# master-v1_0.net
KiCad netlist of a schematic drawn in EAGLE
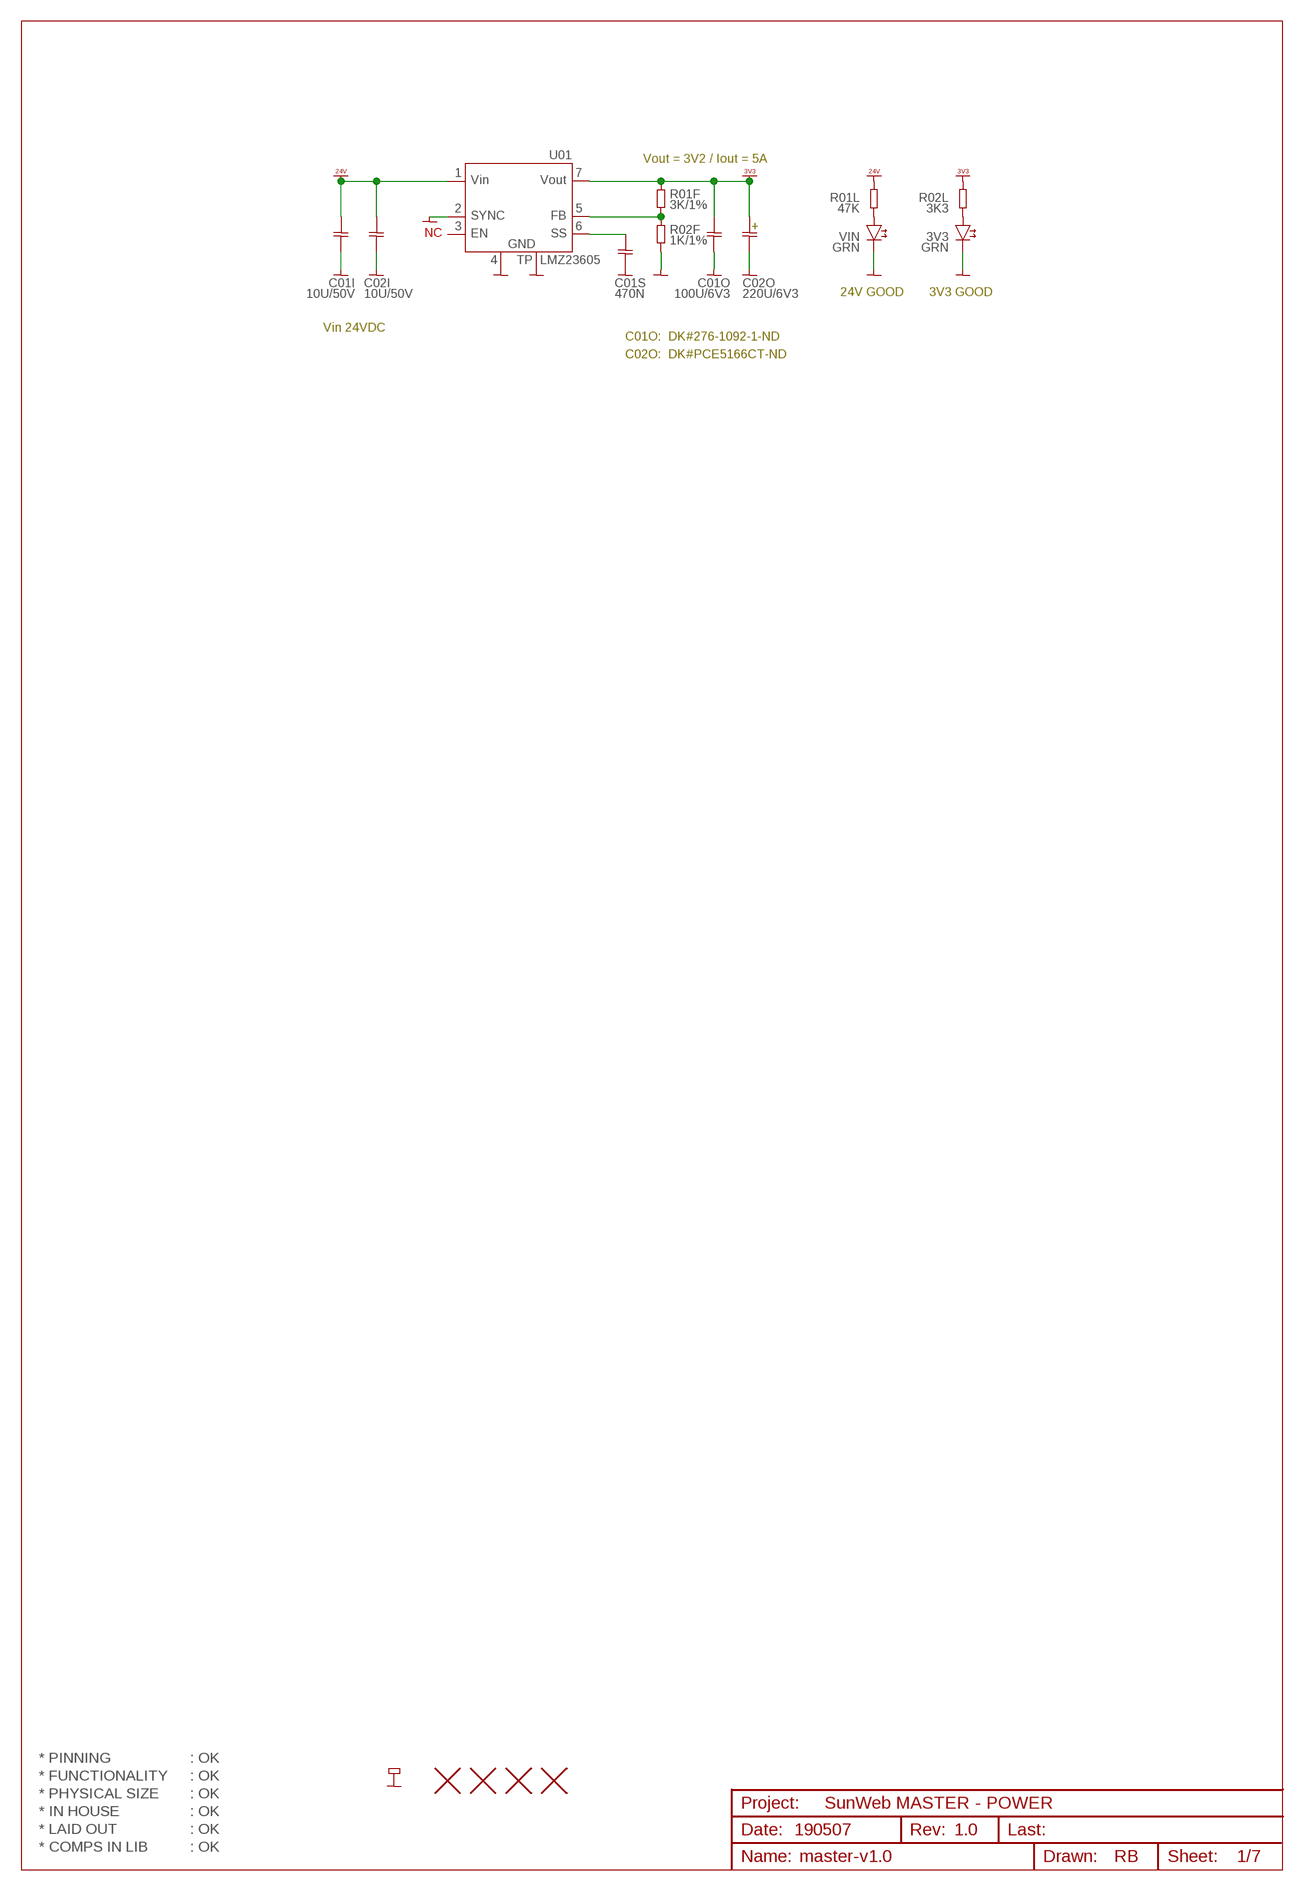
[diagram p0: schematic, sheet 1]
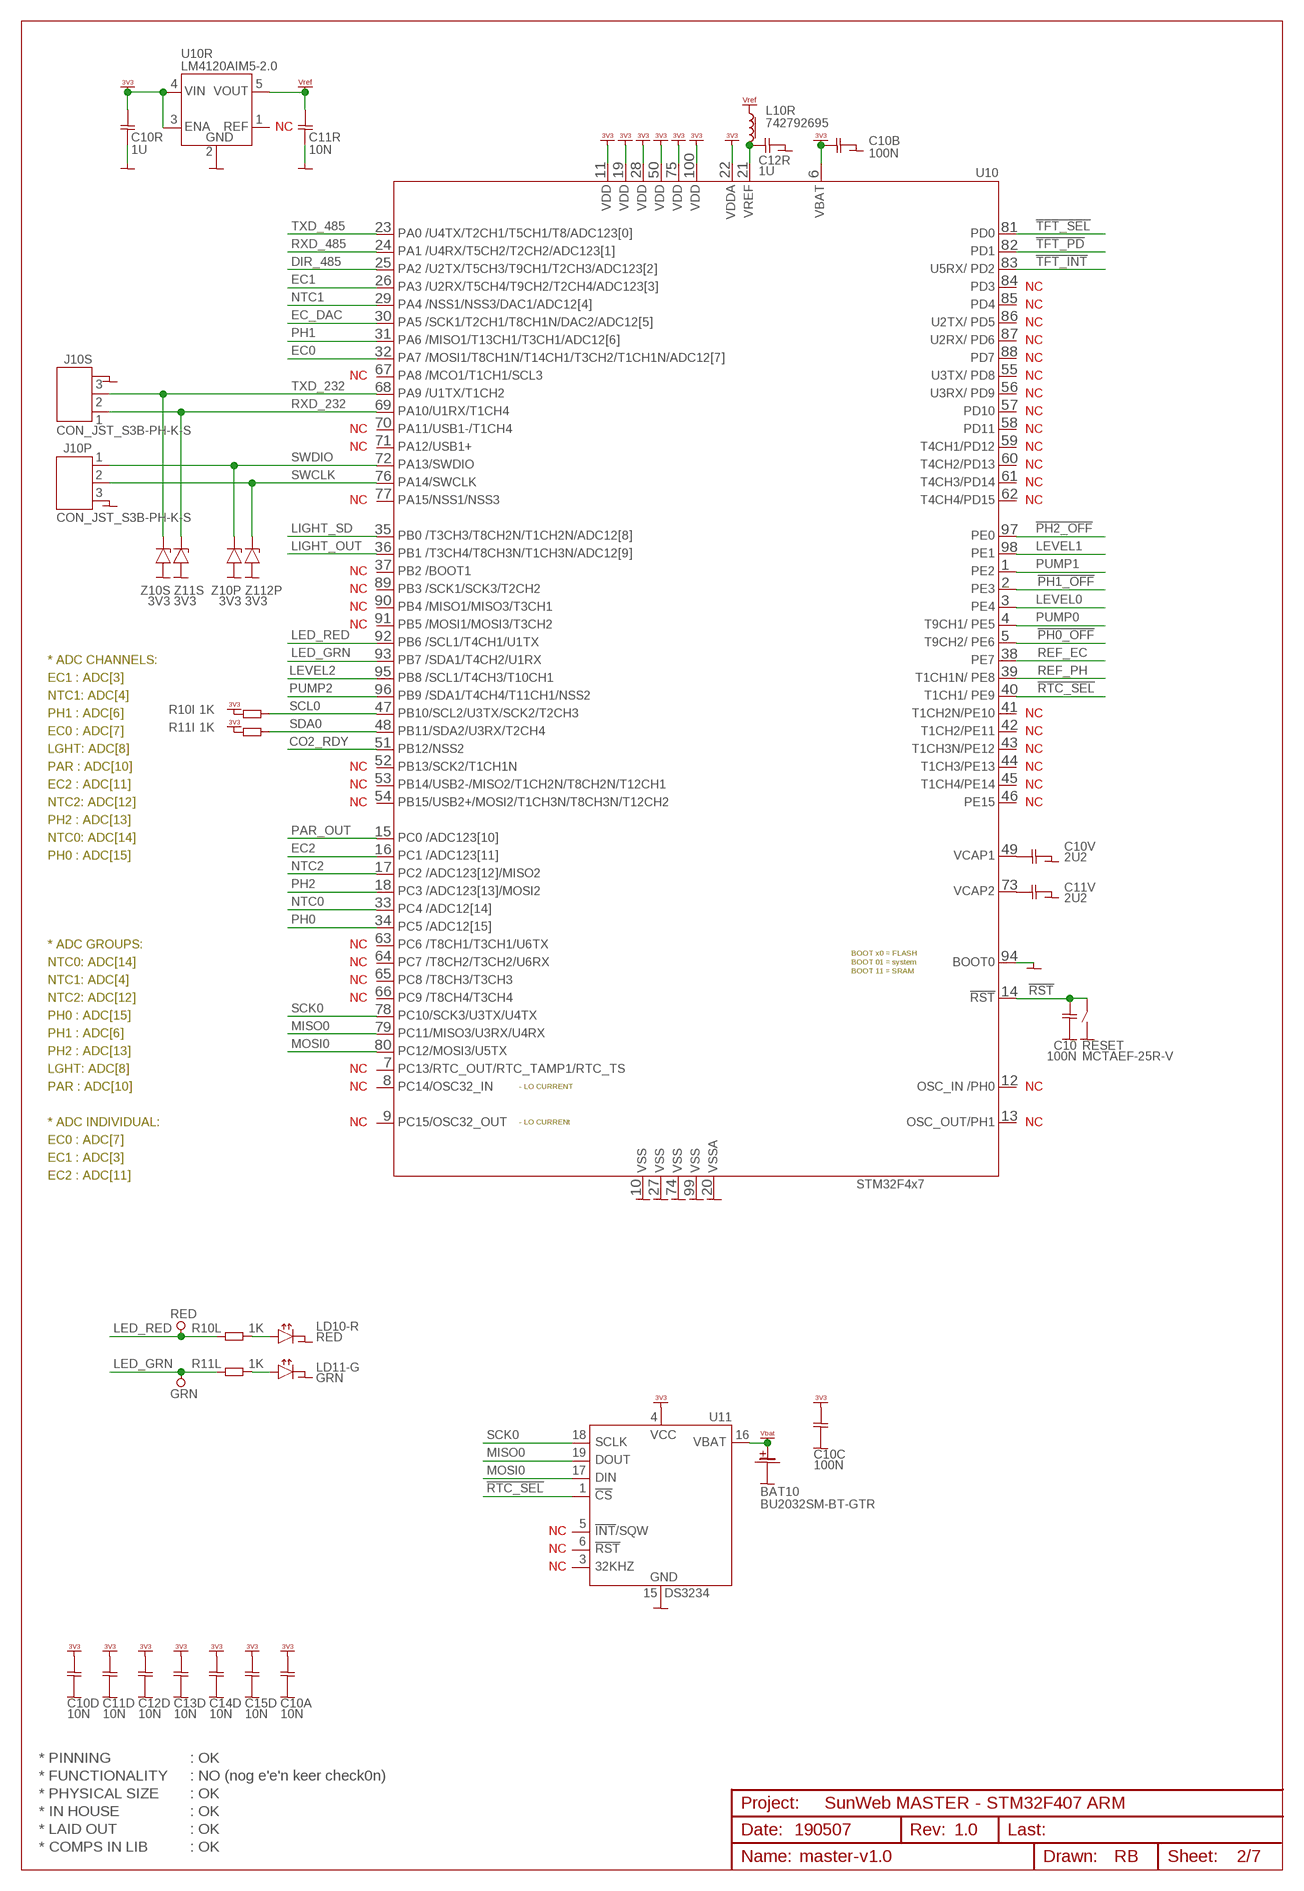
[diagram p1: schematic, sheet 2]
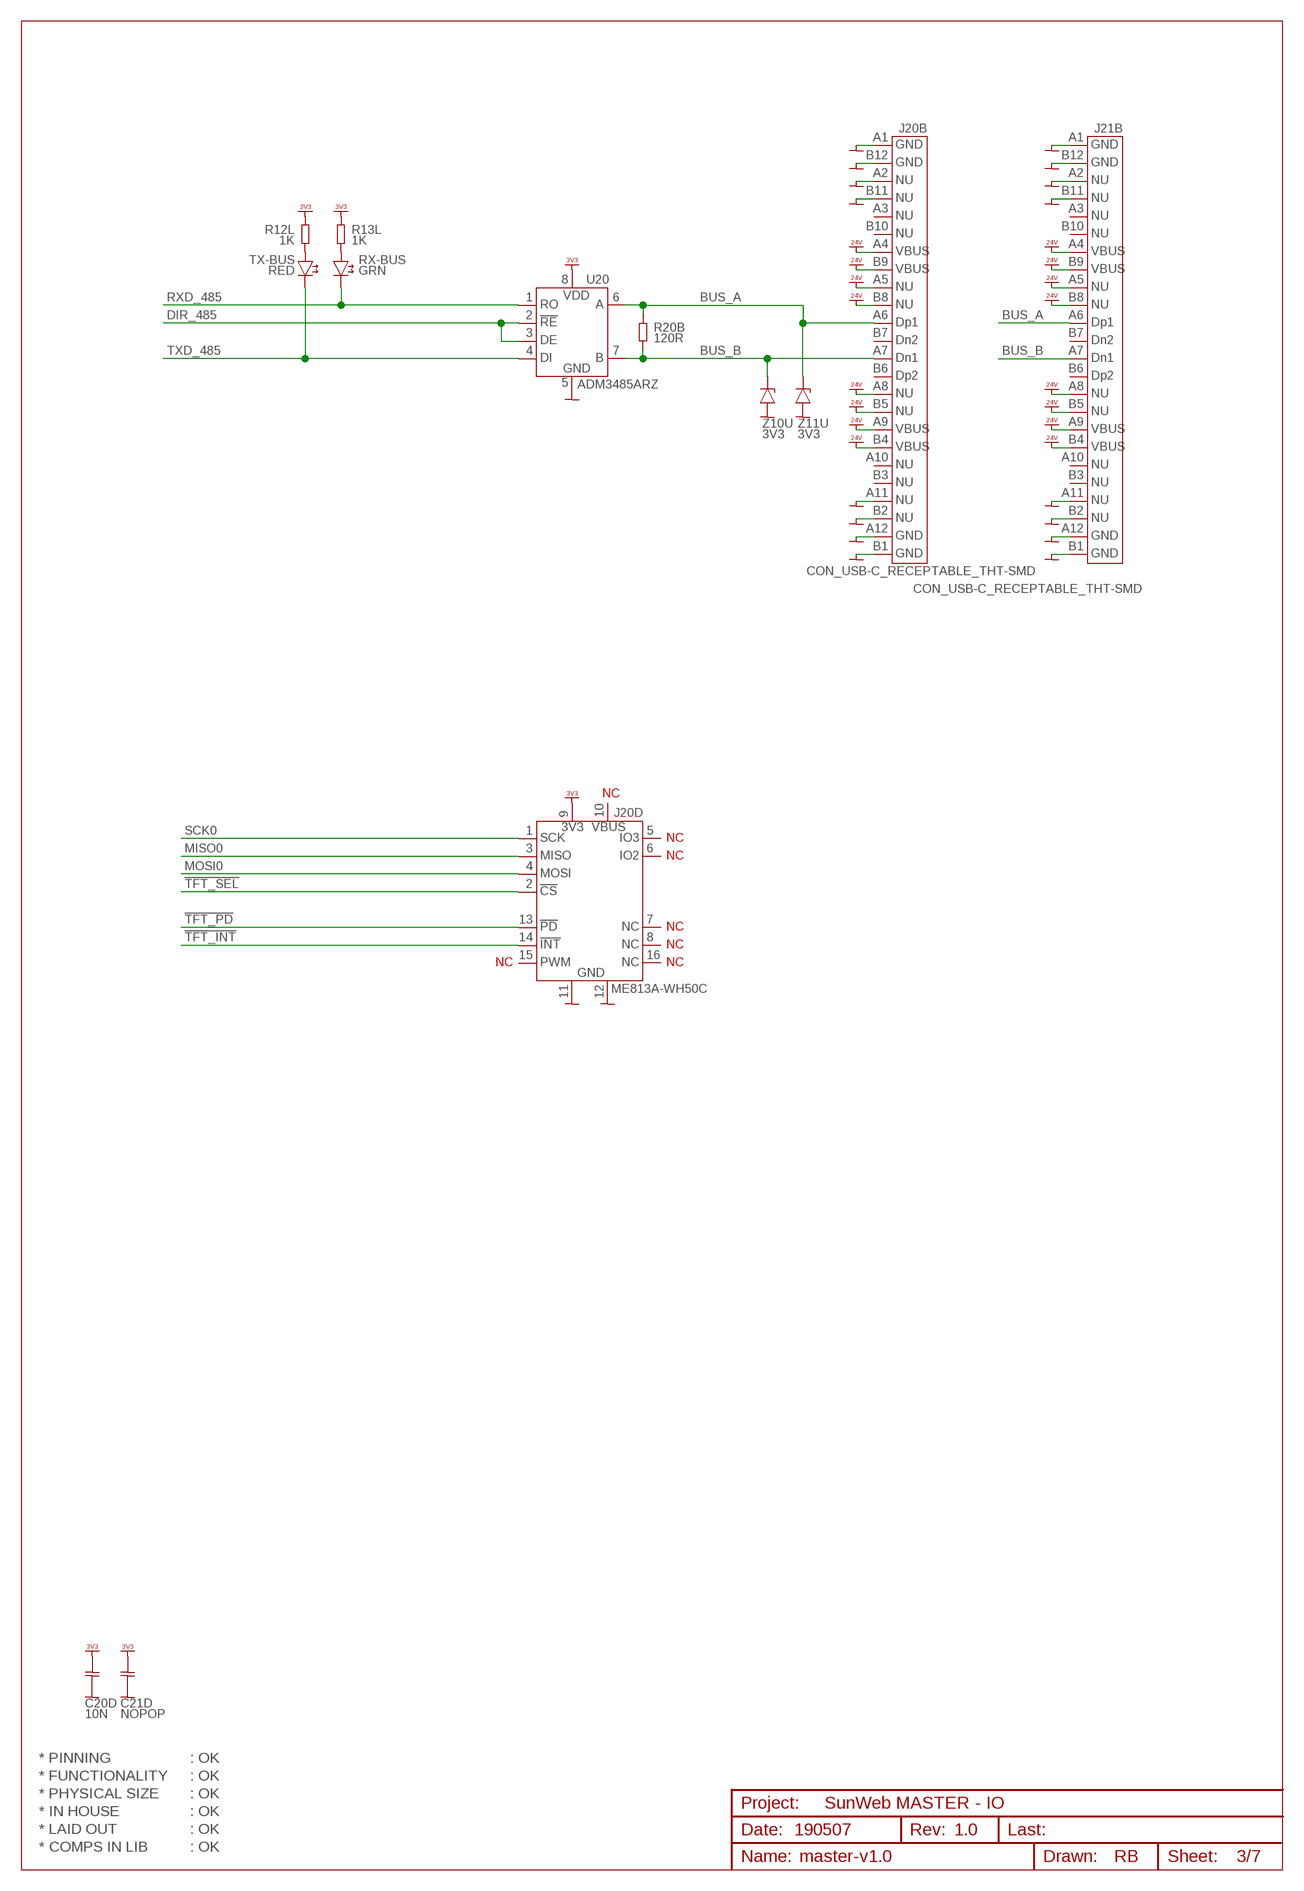
[diagram p2: schematic, sheet 3]
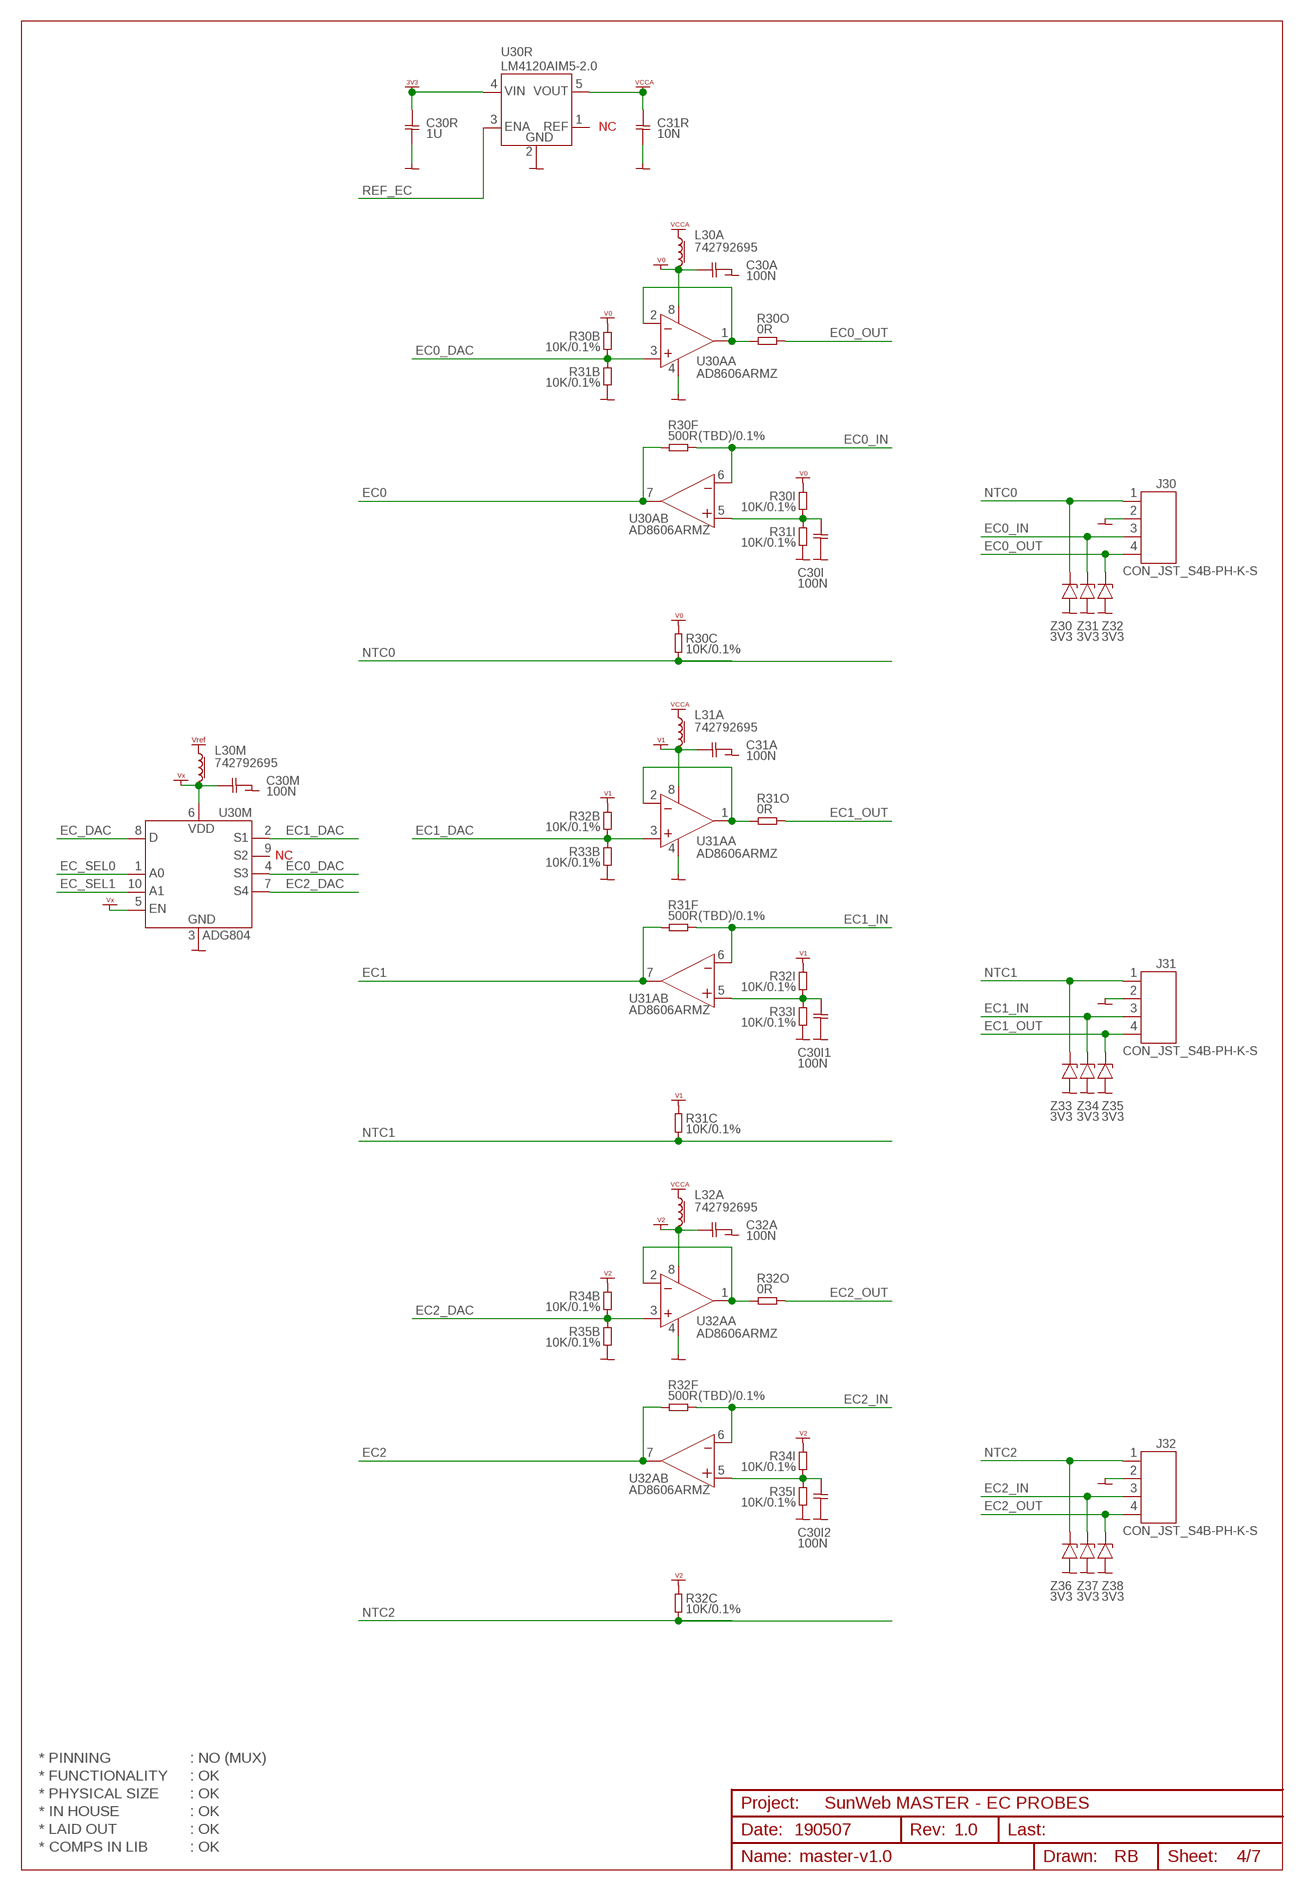
[diagram p3: schematic, sheet 4]
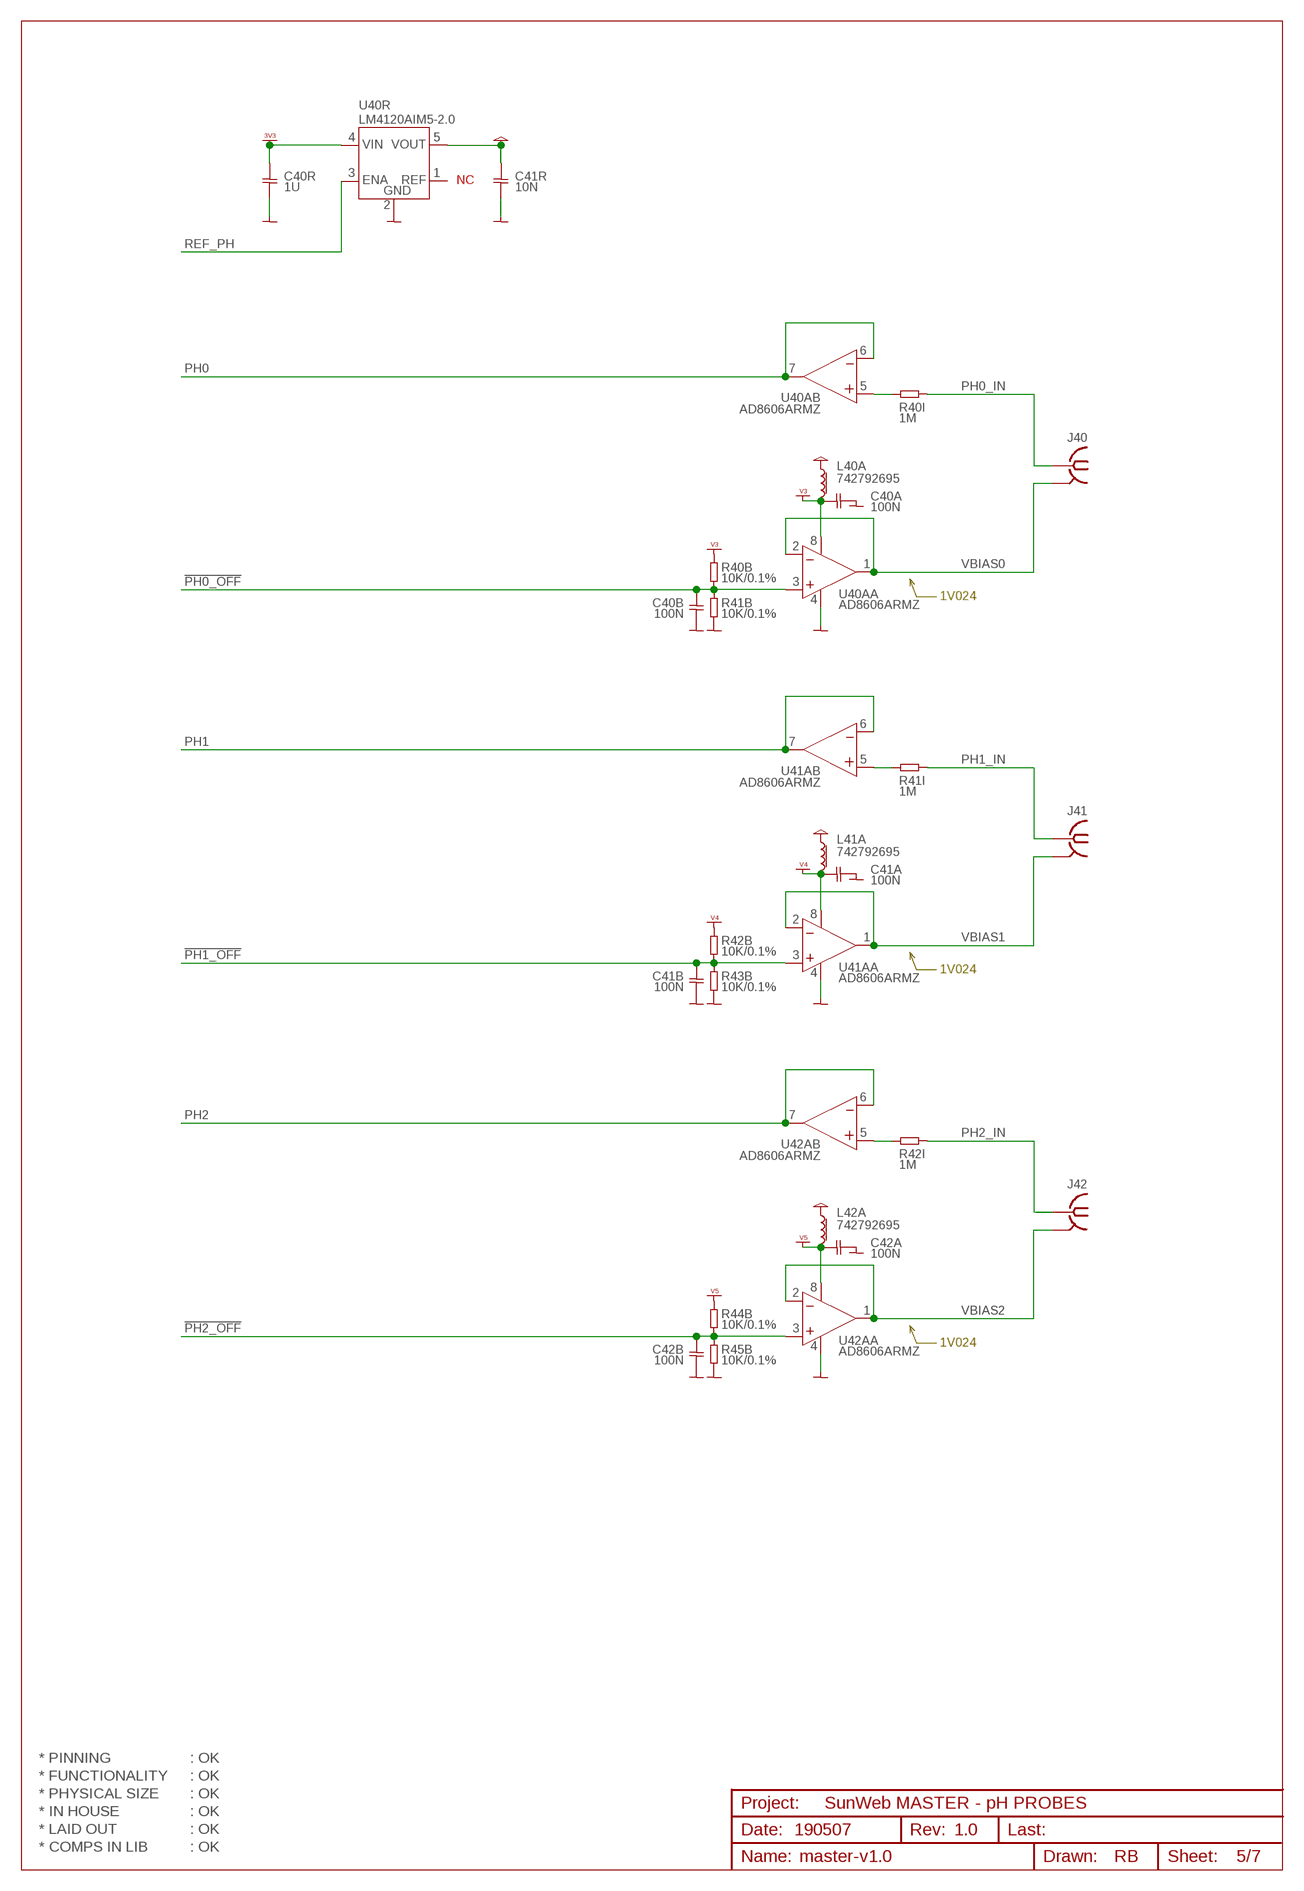
[diagram p4: schematic, sheet 5]
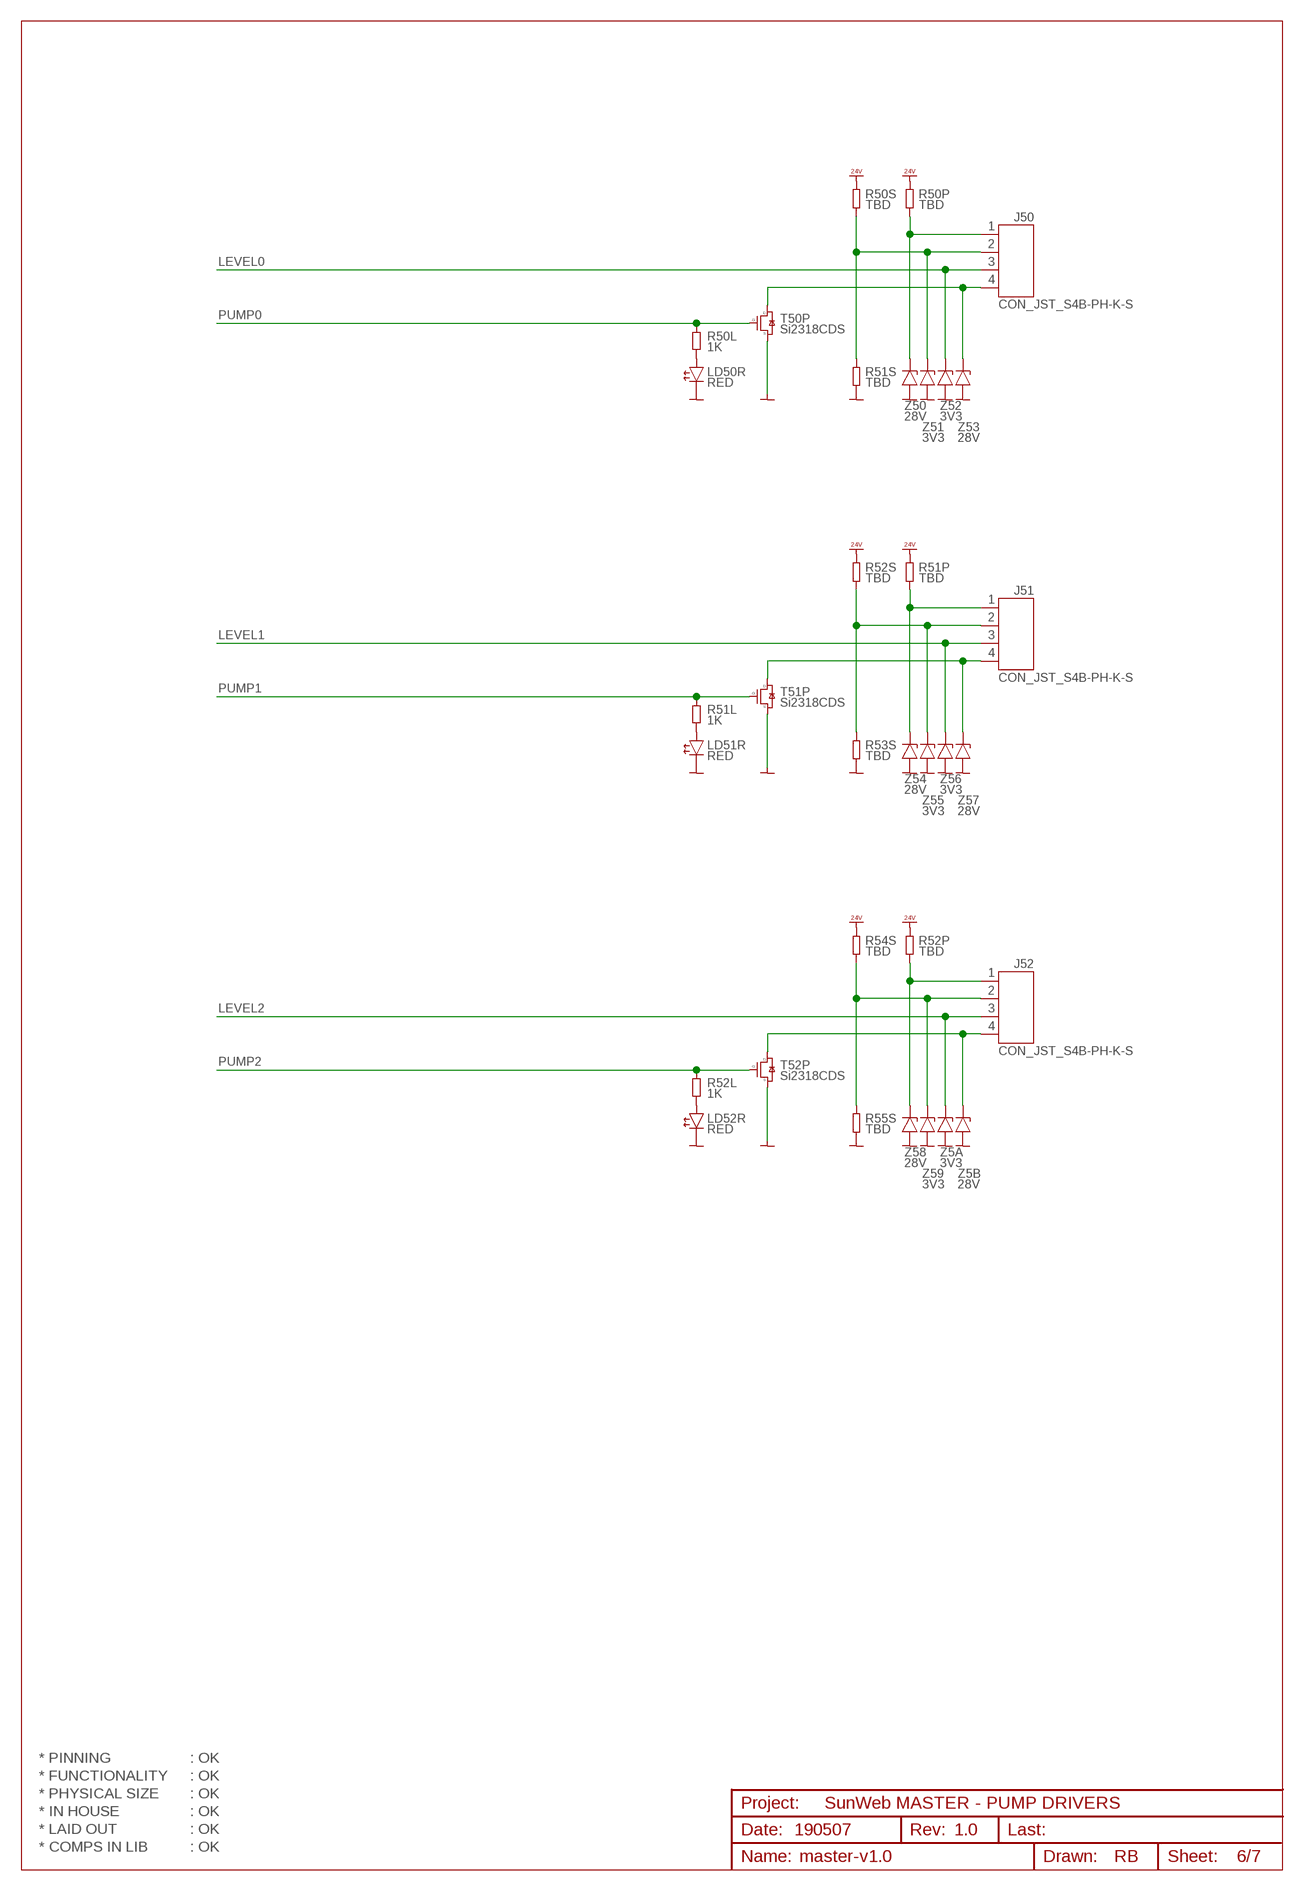
[diagram p5: schematic, sheet 6]
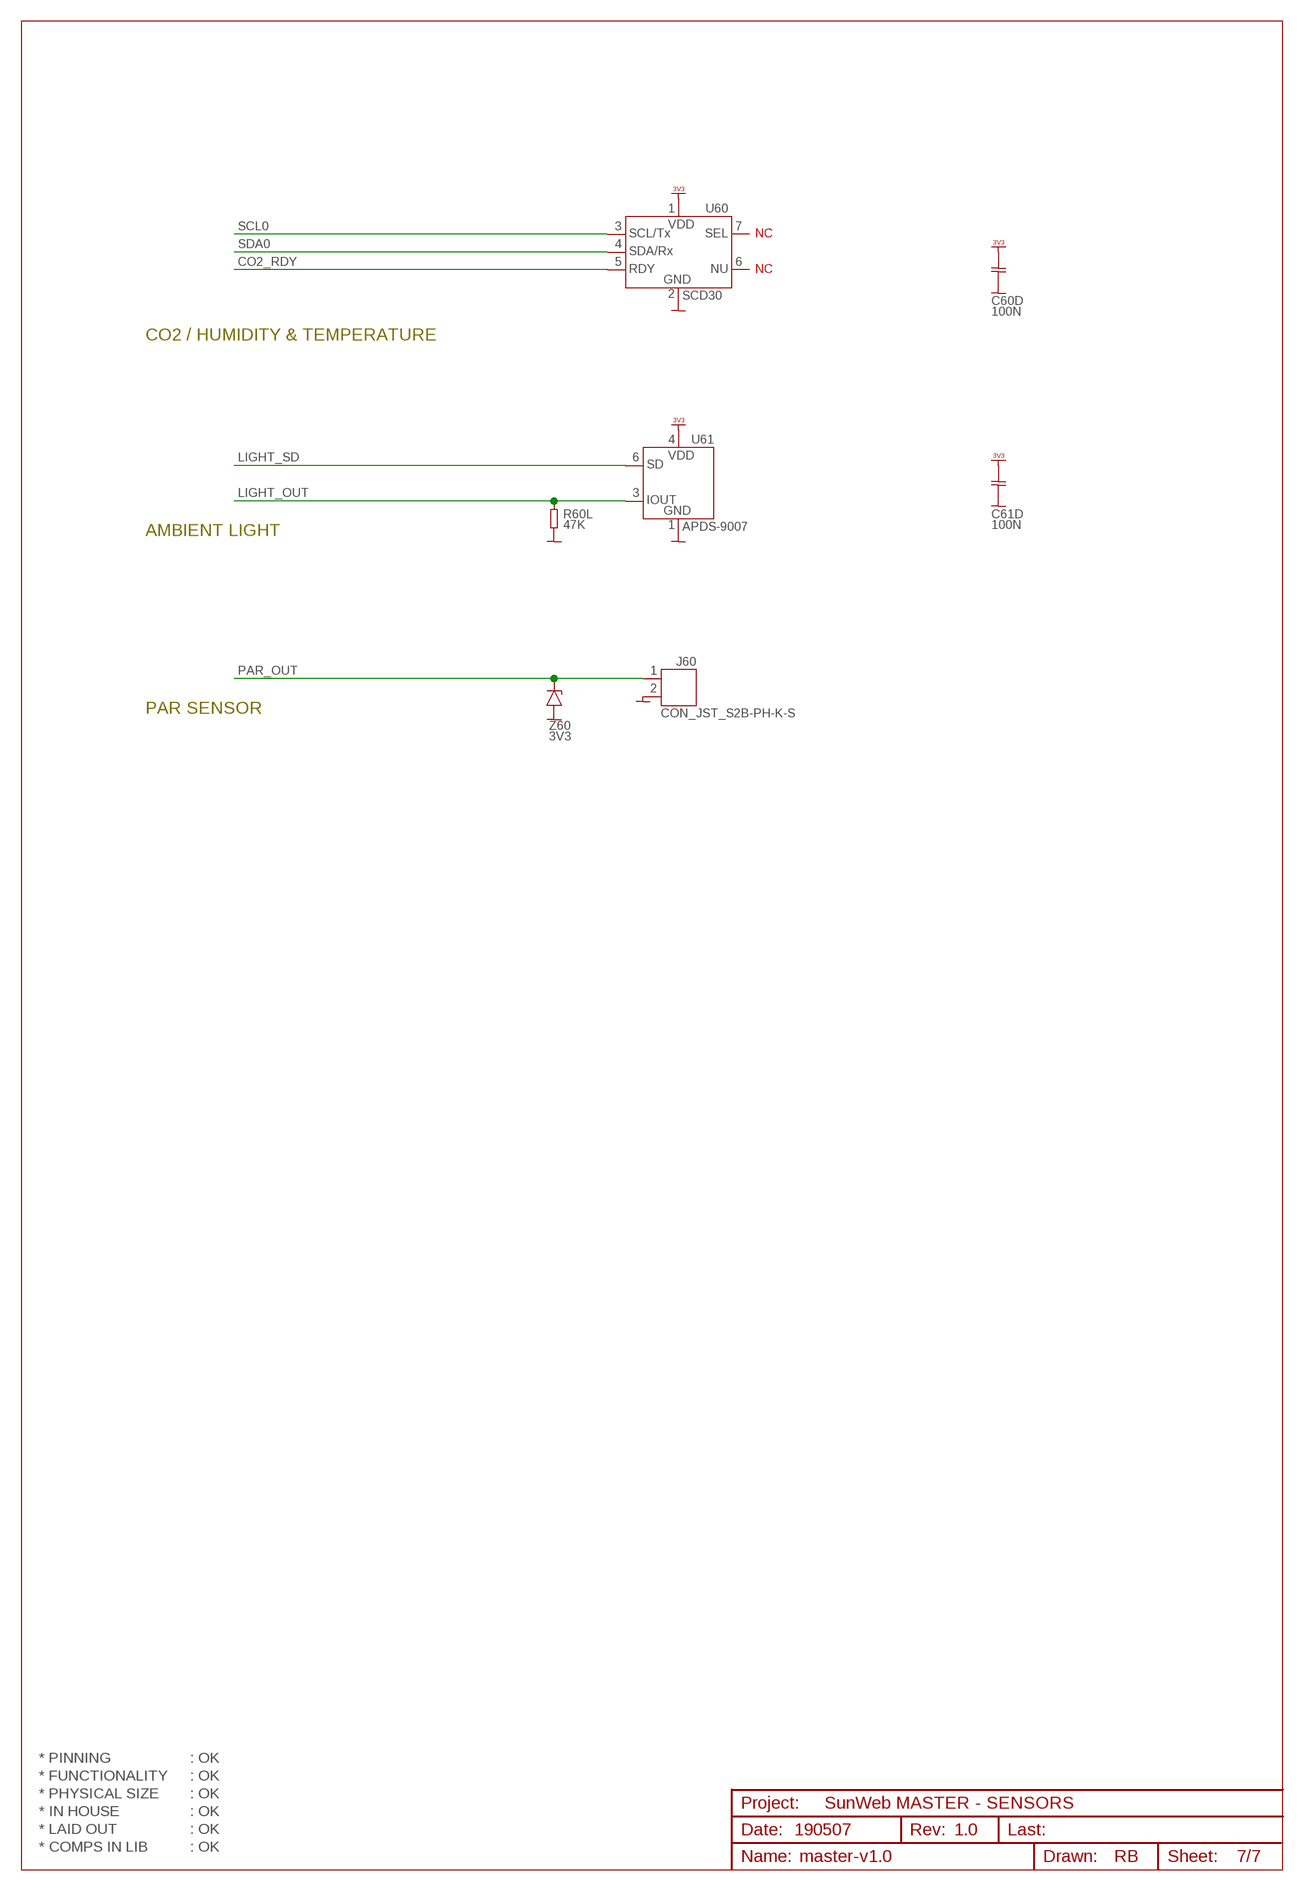
[diagram p6: schematic, sheet 7]

(export (version "E")
  (design (tool "Eeschema 10.0.6"))
  (components
    (comp (ref "C30A")
      (value "100N")
      (footprint "eagle-import:CAP0603")
      (libsource (lib "eagle-import") (part "CAP0603"))
    )
    (comp (ref "C30I")
      (value "100N")
      (footprint "eagle-import:CAP0603")
      (libsource (lib "eagle-import") (part "CAP0603"))
    )
    (comp (ref "C30I1")
      (value "100N")
      (footprint "eagle-import:CAP0603")
      (libsource (lib "eagle-import") (part "CAP0603"))
    )
    (comp (ref "C30I2")
      (value "100N")
      (footprint "eagle-import:CAP0603")
      (libsource (lib "eagle-import") (part "CAP0603"))
    )
    (comp (ref "C30M")
      (value "100N")
      (footprint "eagle-import:CAP0603")
      (libsource (lib "eagle-import") (part "CAP0603"))
    )
    (comp (ref "C30R")
      (value "1U")
      (footprint "eagle-import:CAP0603")
      (libsource (lib "eagle-import") (part "CAP0603"))
    )
    (comp (ref "C31A")
      (value "100N")
      (footprint "eagle-import:CAP0603")
      (libsource (lib "eagle-import") (part "CAP0603"))
    )
    (comp (ref "C31R")
      (value "10N")
      (footprint "eagle-import:CAP0603")
      (libsource (lib "eagle-import") (part "CAP0603"))
    )
    (comp (ref "C32A")
      (value "100N")
      (footprint "eagle-import:CAP0603")
      (libsource (lib "eagle-import") (part "CAP0603"))
    )
    (comp (ref "J30")
      (value "CON_JST_S4B-PH-K-S")
      (footprint "eagle-import:CON_JST_S4B-PH-K-S")
      (libsource (lib "eagle-import") (part "CON_JST_S4B-PH-K-S"))
    )
    (comp (ref "J31")
      (value "CON_JST_S4B-PH-K-S")
      (footprint "eagle-import:CON_JST_S4B-PH-K-S")
      (libsource (lib "eagle-import") (part "CON_JST_S4B-PH-K-S"))
    )
    (comp (ref "J32")
      (value "CON_JST_S4B-PH-K-S")
      (footprint "eagle-import:CON_JST_S4B-PH-K-S")
      (libsource (lib "eagle-import") (part "CON_JST_S4B-PH-K-S"))
    )
    (comp (ref "L30A")
      (value "742792695")
      (footprint "eagle-import:L_0603")
      (libsource (lib "eagle-import") (part "L_0603"))
    )
    (comp (ref "L30M")
      (value "742792695")
      (footprint "eagle-import:L_0603")
      (libsource (lib "eagle-import") (part "L_0603"))
    )
    (comp (ref "L31A")
      (value "742792695")
      (footprint "eagle-import:L_0603")
      (libsource (lib "eagle-import") (part "L_0603"))
    )
    (comp (ref "L32A")
      (value "742792695")
      (footprint "eagle-import:L_0603")
      (libsource (lib "eagle-import") (part "L_0603"))
    )
    (comp (ref "R30B")
      (value "10K/0.1%")
      (footprint "eagle-import:RES0603@2")
      (libsource (lib "eagle-import") (part "00-own_parts_RES0603"))
    )
    (comp (ref "R30C")
      (value "10K/0.1%")
      (footprint "eagle-import:RES0603@2")
      (libsource (lib "eagle-import") (part "00-own_parts_RES0603"))
    )
    (comp (ref "R30F")
      (value "500R(TBD)/0.1%")
      (footprint "eagle-import:RES0603@2")
      (libsource (lib "eagle-import") (part "00-own_parts_RES0603"))
    )
    (comp (ref "R30I")
      (value "10K/0.1%")
      (footprint "eagle-import:RES0603@2")
      (libsource (lib "eagle-import") (part "00-own_parts_RES0603"))
    )
    (comp (ref "R30O")
      (value "0R")
      (footprint "eagle-import:RES0603@2")
      (libsource (lib "eagle-import") (part "00-own_parts_RES0603"))
    )
    (comp (ref "R31B")
      (value "10K/0.1%")
      (footprint "eagle-import:RES0603@2")
      (libsource (lib "eagle-import") (part "00-own_parts_RES0603"))
    )
    (comp (ref "R31C")
      (value "10K/0.1%")
      (footprint "eagle-import:RES0603@2")
      (libsource (lib "eagle-import") (part "00-own_parts_RES0603"))
    )
    (comp (ref "R31F")
      (value "500R(TBD)/0.1%")
      (footprint "eagle-import:RES0603@2")
      (libsource (lib "eagle-import") (part "00-own_parts_RES0603"))
    )
    (comp (ref "R31I")
      (value "10K/0.1%")
      (footprint "eagle-import:RES0603@2")
      (libsource (lib "eagle-import") (part "00-own_parts_RES0603"))
    )
    (comp (ref "R31O")
      (value "0R")
      (footprint "eagle-import:RES0603@2")
      (libsource (lib "eagle-import") (part "00-own_parts_RES0603"))
    )
    (comp (ref "R32B")
      (value "10K/0.1%")
      (footprint "eagle-import:RES0603@2")
      (libsource (lib "eagle-import") (part "00-own_parts_RES0603"))
    )
    (comp (ref "R32C")
      (value "10K/0.1%")
      (footprint "eagle-import:RES0603@2")
      (libsource (lib "eagle-import") (part "00-own_parts_RES0603"))
    )
    (comp (ref "R32F")
      (value "500R(TBD)/0.1%")
      (footprint "eagle-import:RES0603@2")
      (libsource (lib "eagle-import") (part "00-own_parts_RES0603"))
    )
    (comp (ref "R32I")
      (value "10K/0.1%")
      (footprint "eagle-import:RES0603@2")
      (libsource (lib "eagle-import") (part "00-own_parts_RES0603"))
    )
    (comp (ref "R32O")
      (value "0R")
      (footprint "eagle-import:RES0603@2")
      (libsource (lib "eagle-import") (part "00-own_parts_RES0603"))
    )
    (comp (ref "R33B")
      (value "10K/0.1%")
      (footprint "eagle-import:RES0603@2")
      (libsource (lib "eagle-import") (part "00-own_parts_RES0603"))
    )
    (comp (ref "R33I")
      (value "10K/0.1%")
      (footprint "eagle-import:RES0603@2")
      (libsource (lib "eagle-import") (part "00-own_parts_RES0603"))
    )
    (comp (ref "R34B")
      (value "10K/0.1%")
      (footprint "eagle-import:RES0603@2")
      (libsource (lib "eagle-import") (part "00-own_parts_RES0603"))
    )
    (comp (ref "R34I")
      (value "10K/0.1%")
      (footprint "eagle-import:RES0603@2")
      (libsource (lib "eagle-import") (part "00-own_parts_RES0603"))
    )
    (comp (ref "R35B")
      (value "10K/0.1%")
      (footprint "eagle-import:RES0603@2")
      (libsource (lib "eagle-import") (part "00-own_parts_RES0603"))
    )
    (comp (ref "R35I")
      (value "10K/0.1%")
      (footprint "eagle-import:RES0603@2")
      (libsource (lib "eagle-import") (part "00-own_parts_RES0603"))
    )
    (comp (ref "U30A")
      (value "AD8606ARMZ")
      (footprint "eagle-import:MSOP8")
      (libsource (lib "eagle-import") (part "AD8606ARMZ"))
    )
    (comp (ref "U30M")
      (value "ADG804")
      (footprint "eagle-import:MSOP10")
      (libsource (lib "eagle-import") (part "ADG804"))
    )
    (comp (ref "U30R")
      (value "LM4120AIM5-2.0")
      (footprint "eagle-import:SOT23-5")
      (libsource (lib "eagle-import") (part "LM4120AIM5-2.0"))
    )
    (comp (ref "U31A")
      (value "AD8606ARMZ")
      (footprint "eagle-import:MSOP8")
      (libsource (lib "eagle-import") (part "AD8606ARMZ"))
    )
    (comp (ref "U32A")
      (value "AD8606ARMZ")
      (footprint "eagle-import:MSOP8")
      (libsource (lib "eagle-import") (part "AD8606ARMZ"))
    )
    (comp (ref "Z30")
      (value "3V3")
      (footprint "eagle-import:ZENER_SOD80")
      (libsource (lib "eagle-import") (part "ZENER_SOD80"))
    )
    (comp (ref "Z31")
      (value "3V3")
      (footprint "eagle-import:ZENER_SOD80")
      (libsource (lib "eagle-import") (part "ZENER_SOD80"))
    )
    (comp (ref "Z32")
      (value "3V3")
      (footprint "eagle-import:ZENER_SOD80")
      (libsource (lib "eagle-import") (part "ZENER_SOD80"))
    )
    (comp (ref "Z33")
      (value "3V3")
      (footprint "eagle-import:ZENER_SOD80")
      (libsource (lib "eagle-import") (part "ZENER_SOD80"))
    )
    (comp (ref "Z34")
      (value "3V3")
      (footprint "eagle-import:ZENER_SOD80")
      (libsource (lib "eagle-import") (part "ZENER_SOD80"))
    )
    (comp (ref "Z35")
      (value "3V3")
      (footprint "eagle-import:ZENER_SOD80")
      (libsource (lib "eagle-import") (part "ZENER_SOD80"))
    )
    (comp (ref "Z36")
      (value "3V3")
      (footprint "eagle-import:ZENER_SOD80")
      (libsource (lib "eagle-import") (part "ZENER_SOD80"))
    )
    (comp (ref "Z37")
      (value "3V3")
      (footprint "eagle-import:ZENER_SOD80")
      (libsource (lib "eagle-import") (part "ZENER_SOD80"))
    )
    (comp (ref "Z38")
      (value "3V3")
      (footprint "eagle-import:ZENER_SOD80")
      (libsource (lib "eagle-import") (part "ZENER_SOD80"))
    )
    (comp (ref "C40A")
      (value "100N")
      (footprint "eagle-import:CAP0603")
      (libsource (lib "eagle-import") (part "CAP0603"))
    )
    (comp (ref "C40B")
      (value "100N")
      (footprint "eagle-import:CAP0603")
      (libsource (lib "eagle-import") (part "CAP0603"))
    )
    (comp (ref "C40R")
      (value "1U")
      (footprint "eagle-import:CAP0603")
      (libsource (lib "eagle-import") (part "CAP0603"))
    )
    (comp (ref "C41A")
      (value "100N")
      (footprint "eagle-import:CAP0603")
      (libsource (lib "eagle-import") (part "CAP0603"))
    )
    (comp (ref "C41B")
      (value "100N")
      (footprint "eagle-import:CAP0603")
      (libsource (lib "eagle-import") (part "CAP0603"))
    )
    (comp (ref "C41R")
      (value "10N")
      (footprint "eagle-import:CAP0603")
      (libsource (lib "eagle-import") (part "CAP0603"))
    )
    (comp (ref "C42A")
      (value "100N")
      (footprint "eagle-import:CAP0603")
      (libsource (lib "eagle-import") (part "CAP0603"))
    )
    (comp (ref "C42B")
      (value "100N")
      (footprint "eagle-import:CAP0603")
      (libsource (lib "eagle-import") (part "CAP0603"))
    )
    (comp (ref "J40")
      (value "CON_SMA_EDGE_PCB_WIDE_4_CPW")
      (footprint "eagle-import:SMA_LAUNCH_WIDE_4LAYER_CPW")
      (libsource (lib "eagle-import") (part "CON_SMA_EDGE_PCB_WIDE_4_CPW"))
    )
    (comp (ref "J41")
      (value "CON_SMA_EDGE_PCB_WIDE_4_CPW")
      (footprint "eagle-import:SMA_LAUNCH_WIDE_4LAYER_CPW")
      (libsource (lib "eagle-import") (part "CON_SMA_EDGE_PCB_WIDE_4_CPW"))
    )
    (comp (ref "J42")
      (value "CON_SMA_EDGE_PCB_WIDE_4_CPW")
      (footprint "eagle-import:SMA_LAUNCH_WIDE_4LAYER_CPW")
      (libsource (lib "eagle-import") (part "CON_SMA_EDGE_PCB_WIDE_4_CPW"))
    )
    (comp (ref "L40A")
      (value "742792695")
      (footprint "eagle-import:L_0603")
      (libsource (lib "eagle-import") (part "L_0603"))
    )
    (comp (ref "L41A")
      (value "742792695")
      (footprint "eagle-import:L_0603")
      (libsource (lib "eagle-import") (part "L_0603"))
    )
    (comp (ref "L42A")
      (value "742792695")
      (footprint "eagle-import:L_0603")
      (libsource (lib "eagle-import") (part "L_0603"))
    )
    (comp (ref "R40B")
      (value "10K/0.1%")
      (footprint "eagle-import:RES0603@2")
      (libsource (lib "eagle-import") (part "00-own_parts_RES0603"))
    )
    (comp (ref "R40I")
      (value "1M")
      (footprint "eagle-import:RES0603@2")
      (libsource (lib "eagle-import") (part "00-own_parts_RES0603"))
    )
    (comp (ref "R41B")
      (value "10K/0.1%")
      (footprint "eagle-import:RES0603@2")
      (libsource (lib "eagle-import") (part "00-own_parts_RES0603"))
    )
    (comp (ref "R41I")
      (value "1M")
      (footprint "eagle-import:RES0603@2")
      (libsource (lib "eagle-import") (part "00-own_parts_RES0603"))
    )
    (comp (ref "R42B")
      (value "10K/0.1%")
      (footprint "eagle-import:RES0603@2")
      (libsource (lib "eagle-import") (part "00-own_parts_RES0603"))
    )
    (comp (ref "R42I")
      (value "1M")
      (footprint "eagle-import:RES0603@2")
      (libsource (lib "eagle-import") (part "00-own_parts_RES0603"))
    )
    (comp (ref "R43B")
      (value "10K/0.1%")
      (footprint "eagle-import:RES0603@2")
      (libsource (lib "eagle-import") (part "00-own_parts_RES0603"))
    )
    (comp (ref "R44B")
      (value "10K/0.1%")
      (footprint "eagle-import:RES0603@2")
      (libsource (lib "eagle-import") (part "00-own_parts_RES0603"))
    )
    (comp (ref "R45B")
      (value "10K/0.1%")
      (footprint "eagle-import:RES0603@2")
      (libsource (lib "eagle-import") (part "00-own_parts_RES0603"))
    )
    (comp (ref "U40A")
      (value "AD8606ARMZ")
      (footprint "eagle-import:MSOP8")
      (libsource (lib "eagle-import") (part "AD8606ARMZ"))
    )
    (comp (ref "U40R")
      (value "LM4120AIM5-2.0")
      (footprint "eagle-import:SOT23-5")
      (libsource (lib "eagle-import") (part "LM4120AIM5-2.0"))
    )
    (comp (ref "U41A")
      (value "AD8606ARMZ")
      (footprint "eagle-import:MSOP8")
      (libsource (lib "eagle-import") (part "AD8606ARMZ"))
    )
    (comp (ref "U42A")
      (value "AD8606ARMZ")
      (footprint "eagle-import:MSOP8")
      (libsource (lib "eagle-import") (part "AD8606ARMZ"))
    )
    (comp (ref "J50")
      (value "CON_JST_S4B-PH-K-S")
      (footprint "eagle-import:CON_JST_S4B-PH-K-S")
      (libsource (lib "eagle-import") (part "CON_JST_S4B-PH-K-S"))
    )
    (comp (ref "J51")
      (value "CON_JST_S4B-PH-K-S")
      (footprint "eagle-import:CON_JST_S4B-PH-K-S")
      (libsource (lib "eagle-import") (part "CON_JST_S4B-PH-K-S"))
    )
    (comp (ref "J52")
      (value "CON_JST_S4B-PH-K-S")
      (footprint "eagle-import:CON_JST_S4B-PH-K-S")
      (libsource (lib "eagle-import") (part "CON_JST_S4B-PH-K-S"))
    )
    (comp (ref "LD50R")
      (value "RED")
      (footprint "eagle-import:LED_SMD_0603")
      (libsource (lib "eagle-import") (part "LED_SMD_0603"))
    )
    (comp (ref "LD51R")
      (value "RED")
      (footprint "eagle-import:LED_SMD_0603")
      (libsource (lib "eagle-import") (part "LED_SMD_0603"))
    )
    (comp (ref "LD52R")
      (value "RED")
      (footprint "eagle-import:LED_SMD_0603")
      (libsource (lib "eagle-import") (part "LED_SMD_0603"))
    )
    (comp (ref "R50L")
      (value "1K")
      (footprint "eagle-import:RES0603@2")
      (libsource (lib "eagle-import") (part "00-own_parts_RES0603"))
    )
    (comp (ref "R50P")
      (value "TBD")
      (footprint "eagle-import:RES0805")
      (libsource (lib "eagle-import") (part "RES0805"))
    )
    (comp (ref "R50S")
      (value "TBD")
      (footprint "eagle-import:RES0603@2")
      (libsource (lib "eagle-import") (part "00-own_parts_RES0603"))
    )
    (comp (ref "R51L")
      (value "1K")
      (footprint "eagle-import:RES0603@2")
      (libsource (lib "eagle-import") (part "00-own_parts_RES0603"))
    )
    (comp (ref "R51P")
      (value "TBD")
      (footprint "eagle-import:RES0805")
      (libsource (lib "eagle-import") (part "RES0805"))
    )
    (comp (ref "R51S")
      (value "TBD")
      (footprint "eagle-import:RES0603@2")
      (libsource (lib "eagle-import") (part "00-own_parts_RES0603"))
    )
    (comp (ref "R52L")
      (value "1K")
      (footprint "eagle-import:RES0603@2")
      (libsource (lib "eagle-import") (part "00-own_parts_RES0603"))
    )
    (comp (ref "R52P")
      (value "TBD")
      (footprint "eagle-import:RES0805")
      (libsource (lib "eagle-import") (part "RES0805"))
    )
    (comp (ref "R52S")
      (value "TBD")
      (footprint "eagle-import:RES0603@2")
      (libsource (lib "eagle-import") (part "00-own_parts_RES0603"))
    )
    (comp (ref "R53S")
      (value "TBD")
      (footprint "eagle-import:RES0603@2")
      (libsource (lib "eagle-import") (part "00-own_parts_RES0603"))
    )
    (comp (ref "R54S")
      (value "TBD")
      (footprint "eagle-import:RES0603@2")
      (libsource (lib "eagle-import") (part "00-own_parts_RES0603"))
    )
    (comp (ref "R55S")
      (value "TBD")
      (footprint "eagle-import:RES0603@2")
      (libsource (lib "eagle-import") (part "00-own_parts_RES0603"))
    )
    (comp (ref "T50P")
      (value "Si2318CDS")
      (footprint "eagle-import:NFET_SOT23")
      (libsource (lib "eagle-import") (part "NFET_SOT23"))
    )
    (comp (ref "T51P")
      (value "Si2318CDS")
      (footprint "eagle-import:NFET_SOT23")
      (libsource (lib "eagle-import") (part "NFET_SOT23"))
    )
    (comp (ref "T52P")
      (value "Si2318CDS")
      (footprint "eagle-import:NFET_SOT23")
      (libsource (lib "eagle-import") (part "NFET_SOT23"))
    )
    (comp (ref "Z5A")
      (value "3V3")
      (footprint "eagle-import:ZENER_SOD80")
      (libsource (lib "eagle-import") (part "ZENER_SOD80"))
    )
    (comp (ref "Z5B")
      (value "28V")
      (footprint "eagle-import:ZENER_SOD80")
      (libsource (lib "eagle-import") (part "ZENER_SOD80"))
    )
    (comp (ref "Z50")
      (value "28V")
      (footprint "eagle-import:ZENER_SOD80")
      (libsource (lib "eagle-import") (part "ZENER_SOD80"))
    )
    (comp (ref "Z51")
      (value "3V3")
      (footprint "eagle-import:ZENER_SOD80")
      (libsource (lib "eagle-import") (part "ZENER_SOD80"))
    )
    (comp (ref "Z52")
      (value "3V3")
      (footprint "eagle-import:ZENER_SOD80")
      (libsource (lib "eagle-import") (part "ZENER_SOD80"))
    )
    (comp (ref "Z53")
      (value "28V")
      (footprint "eagle-import:ZENER_SOD80")
      (libsource (lib "eagle-import") (part "ZENER_SOD80"))
    )
    (comp (ref "Z54")
      (value "28V")
      (footprint "eagle-import:ZENER_SOD80")
      (libsource (lib "eagle-import") (part "ZENER_SOD80"))
    )
    (comp (ref "Z55")
      (value "3V3")
      (footprint "eagle-import:ZENER_SOD80")
      (libsource (lib "eagle-import") (part "ZENER_SOD80"))
    )
    (comp (ref "Z56")
      (value "3V3")
      (footprint "eagle-import:ZENER_SOD80")
      (libsource (lib "eagle-import") (part "ZENER_SOD80"))
    )
    (comp (ref "Z57")
      (value "28V")
      (footprint "eagle-import:ZENER_SOD80")
      (libsource (lib "eagle-import") (part "ZENER_SOD80"))
    )
    (comp (ref "Z58")
      (value "28V")
      (footprint "eagle-import:ZENER_SOD80")
      (libsource (lib "eagle-import") (part "ZENER_SOD80"))
    )
    (comp (ref "Z59")
      (value "3V3")
      (footprint "eagle-import:ZENER_SOD80")
      (libsource (lib "eagle-import") (part "ZENER_SOD80"))
    )
    (comp (ref "3V3")
      (value "GRN")
      (footprint "eagle-import:LED_SMD_0603")
      (libsource (lib "eagle-import") (part "LED_SMD_0603"))
    )
    (comp (ref "C01I")
      (value "10U/50V")
      (footprint "eagle-import:CAP1210")
      (libsource (lib "eagle-import") (part "CAP1210"))
    )
    (comp (ref "C01O")
      (value "100U/6V3")
      (footprint "eagle-import:CAP1210")
      (libsource (lib "eagle-import") (part "CAP1210"))
    )
    (comp (ref "C01S")
      (value "470N")
      (footprint "eagle-import:CAP0603")
      (libsource (lib "eagle-import") (part "CAP0603"))
    )
    (comp (ref "C02I")
      (value "10U/50V")
      (footprint "eagle-import:CAP1210")
      (libsource (lib "eagle-import") (part "CAP1210"))
    )
    (comp (ref "C02O")
      (value "220U/6V3")
      (footprint "eagle-import:CAP2917")
      (libsource (lib "eagle-import") (part "CAP2917"))
    )
    (comp (ref "H1")
      (value "HOLE_NPTH_3.2MM")
      (footprint "eagle-import:HOLE_NPTH_3.2MM")
      (libsource (lib "eagle-import") (part "HOLE_NPTH_3.2MM"))
    )
    (comp (ref "H2")
      (value "HOLE_NPTH_3.2MM")
      (footprint "eagle-import:HOLE_NPTH_3.2MM")
      (libsource (lib "eagle-import") (part "HOLE_NPTH_3.2MM"))
    )
    (comp (ref "H3")
      (value "HOLE_NPTH_3.2MM")
      (footprint "eagle-import:HOLE_NPTH_3.2MM")
      (libsource (lib "eagle-import") (part "HOLE_NPTH_3.2MM"))
    )
    (comp (ref "H4")
      (value "HOLE_NPTH_3.2MM")
      (footprint "eagle-import:HOLE_NPTH_3.2MM")
      (libsource (lib "eagle-import") (part "HOLE_NPTH_3.2MM"))
    )
    (comp (ref "R01F")
      (value "3K/1%")
      (footprint "eagle-import:RES0603@2")
      (libsource (lib "eagle-import") (part "00-own_parts_RES0603"))
    )
    (comp (ref "R01L")
      (value "47K")
      (footprint "eagle-import:RES0603@2")
      (libsource (lib "eagle-import") (part "00-own_parts_RES0603"))
    )
    (comp (ref "R02F")
      (value "1K/1%")
      (footprint "eagle-import:RES0603@2")
      (libsource (lib "eagle-import") (part "00-own_parts_RES0603"))
    )
    (comp (ref "R02L")
      (value "3K3")
      (footprint "eagle-import:RES0603@2")
      (libsource (lib "eagle-import") (part "00-own_parts_RES0603"))
    )
    (comp (ref "TP2")
      (value "PIN_GND")
      (footprint "eagle-import:HOLE_PTH_1.8MM_SQR")
      (libsource (lib "eagle-import") (part "PIN_GND"))
    )
    (comp (ref "U01")
      (value "LMZ23605")
      (footprint "eagle-import:TOPMOD-7")
      (libsource (lib "eagle-import") (part "LMZ23605"))
    )
    (comp (ref "VIN")
      (value "GRN")
      (footprint "eagle-import:LED_SMD_0603")
      (libsource (lib "eagle-import") (part "LED_SMD_0603"))
    )
    (comp (ref "C60D")
      (value "100N")
      (footprint "eagle-import:CAP0603")
      (libsource (lib "eagle-import") (part "CAP0603"))
    )
    (comp (ref "C61D")
      (value "100N")
      (footprint "eagle-import:CAP0603")
      (libsource (lib "eagle-import") (part "CAP0603"))
    )
    (comp (ref "J60")
      (value "CON_JST_S2B-PH-K-S")
      (footprint "eagle-import:CON_JST_S2B-PH-K-S")
      (libsource (lib "eagle-import") (part "CON_JST_S2B-PH-K-S"))
    )
    (comp (ref "R60L")
      (value "47K")
      (footprint "eagle-import:RES0603@2")
      (libsource (lib "eagle-import") (part "00-own_parts_RES0603"))
    )
    (comp (ref "U60")
      (value "SCD30")
      (footprint "eagle-import:SCD30")
      (libsource (lib "eagle-import") (part "SCD30"))
    )
    (comp (ref "U61")
      (value "APDS-9007")
      (footprint "eagle-import:APDS-9007")
      (libsource (lib "eagle-import") (part "APDS-9007"))
    )
    (comp (ref "Z60")
      (value "3V3")
      (footprint "eagle-import:ZENER_SOD80")
      (libsource (lib "eagle-import") (part "ZENER_SOD80"))
    )
    (comp (ref "BAT10")
      (value "BU2032SM-BT-GTR")
      (footprint "eagle-import:BU2032SM-BT-GTR")
      (libsource (lib "eagle-import") (part "BU2032SM-BT-GTR"))
    )
    (comp (ref "C10")
      (value "100N")
      (footprint "eagle-import:CAP0603")
      (libsource (lib "eagle-import") (part "CAP0603"))
    )
    (comp (ref "C10A")
      (value "10N")
      (footprint "eagle-import:CAP0603")
      (libsource (lib "eagle-import") (part "CAP0603"))
    )
    (comp (ref "C10B")
      (value "100N")
      (footprint "eagle-import:CAP0603")
      (libsource (lib "eagle-import") (part "CAP0603"))
    )
    (comp (ref "C10C")
      (value "100N")
      (footprint "eagle-import:CAP0603")
      (libsource (lib "eagle-import") (part "CAP0603"))
    )
    (comp (ref "C10D")
      (value "10N")
      (footprint "eagle-import:CAP0603")
      (libsource (lib "eagle-import") (part "CAP0603"))
    )
    (comp (ref "C10R")
      (value "1U")
      (footprint "eagle-import:CAP0603")
      (libsource (lib "eagle-import") (part "CAP0603"))
    )
    (comp (ref "C10V")
      (value "2U2")
      (footprint "eagle-import:CAP0603")
      (libsource (lib "eagle-import") (part "CAP0603"))
    )
    (comp (ref "C11D")
      (value "10N")
      (footprint "eagle-import:CAP0603")
      (libsource (lib "eagle-import") (part "CAP0603"))
    )
    (comp (ref "C11R")
      (value "10N")
      (footprint "eagle-import:CAP0603")
      (libsource (lib "eagle-import") (part "CAP0603"))
    )
    (comp (ref "C11V")
      (value "2U2")
      (footprint "eagle-import:CAP0603")
      (libsource (lib "eagle-import") (part "CAP0603"))
    )
    (comp (ref "C12D")
      (value "10N")
      (footprint "eagle-import:CAP0603")
      (libsource (lib "eagle-import") (part "CAP0603"))
    )
    (comp (ref "C12R")
      (value "1U")
      (footprint "eagle-import:CAP0603")
      (libsource (lib "eagle-import") (part "CAP0603"))
    )
    (comp (ref "C13D")
      (value "10N")
      (footprint "eagle-import:CAP0603")
      (libsource (lib "eagle-import") (part "CAP0603"))
    )
    (comp (ref "C14D")
      (value "10N")
      (footprint "eagle-import:CAP0603")
      (libsource (lib "eagle-import") (part "CAP0603"))
    )
    (comp (ref "C15D")
      (value "10N")
      (footprint "eagle-import:CAP0603")
      (libsource (lib "eagle-import") (part "CAP0603"))
    )
    (comp (ref "GRN")
      (value "PIN_TEST")
      (footprint "eagle-import:HOLE_PTH_0.8MM")
      (libsource (lib "eagle-import") (part "PIN_TEST"))
    )
    (comp (ref "J10P")
      (value "CON_JST_S3B-PH-K-S")
      (footprint "eagle-import:CON_JST_S3B-PH-K-S")
      (libsource (lib "eagle-import") (part "CON_JST_S3B-PH-K-S"))
    )
    (comp (ref "J10S")
      (value "CON_JST_S3B-PH-K-S")
      (footprint "eagle-import:CON_JST_S3B-PH-K-S")
      (libsource (lib "eagle-import") (part "CON_JST_S3B-PH-K-S"))
    )
    (comp (ref "L10R")
      (value "742792695")
      (footprint "eagle-import:L_0603")
      (libsource (lib "eagle-import") (part "L_0603"))
    )
    (comp (ref "LD10-R")
      (value "RED")
      (footprint "eagle-import:LED_SMD_0603")
      (libsource (lib "eagle-import") (part "LED_SMD_0603"))
    )
    (comp (ref "LD11-G")
      (value "GRN")
      (footprint "eagle-import:LED_SMD_0603")
      (libsource (lib "eagle-import") (part "LED_SMD_0603"))
    )
    (comp (ref "R10I")
      (value "1K")
      (footprint "eagle-import:RES0603@2")
      (libsource (lib "eagle-import") (part "00-own_parts_RES0603"))
    )
    (comp (ref "R10L")
      (value "1K")
      (footprint "eagle-import:RES0603@2")
      (libsource (lib "eagle-import") (part "00-own_parts_RES0603"))
    )
    (comp (ref "R11I")
      (value "1K")
      (footprint "eagle-import:RES0603@2")
      (libsource (lib "eagle-import") (part "00-own_parts_RES0603"))
    )
    (comp (ref "R11L")
      (value "1K")
      (footprint "eagle-import:RES0603@2")
      (libsource (lib "eagle-import") (part "00-own_parts_RES0603"))
    )
    (comp (ref "RED")
      (value "PIN_TEST")
      (footprint "eagle-import:HOLE_PTH_0.8MM")
      (libsource (lib "eagle-import") (part "PIN_TEST"))
    )
    (comp (ref "RESET")
      (value "MCTAEF-25R-V")
      (footprint "eagle-import:SWITCH_SMD_PBUTTON_2P")
      (libsource (lib "eagle-import") (part "SWITCH_PUSHBUTTON"))
    )
    (comp (ref "U10")
      (value "STM32F407VG")
      (footprint "eagle-import:LQFP100")
      (libsource (lib "eagle-import") (part "STM32F407VG"))
    )
    (comp (ref "U10R")
      (value "LM4120AIM5-2.0")
      (footprint "eagle-import:SOT23-5")
      (libsource (lib "eagle-import") (part "LM4120AIM5-2.0"))
    )
    (comp (ref "U11")
      (value "DS3234")
      (footprint "eagle-import:SO20W")
      (libsource (lib "eagle-import") (part "DS3234"))
    )
    (comp (ref "Z10P")
      (value "3V3")
      (footprint "eagle-import:ZENER_SOD80")
      (libsource (lib "eagle-import") (part "ZENER_SOD80"))
    )
    (comp (ref "Z10S")
      (value "3V3")
      (footprint "eagle-import:ZENER_SOD80")
      (libsource (lib "eagle-import") (part "ZENER_SOD80"))
    )
    (comp (ref "Z11S")
      (value "3V3")
      (footprint "eagle-import:ZENER_SOD80")
      (libsource (lib "eagle-import") (part "ZENER_SOD80"))
    )
    (comp (ref "Z112P")
      (value "3V3")
      (footprint "eagle-import:ZENER_SOD80")
      (libsource (lib "eagle-import") (part "ZENER_SOD80"))
    )
    (comp (ref "C20D")
      (value "10N")
      (footprint "eagle-import:CAP0603")
      (libsource (lib "eagle-import") (part "CAP0603"))
    )
    (comp (ref "C21D")
      (value "NOPOP")
      (footprint "eagle-import:CAP1210")
      (libsource (lib "eagle-import") (part "CAP1210"))
    )
    (comp (ref "J20B")
      (value "CON_USB-C_RECEPTABLE_THT-SMD")
      (footprint "eagle-import:CON_USB-C_RECEPTABLE_THT-SMD")
      (libsource (lib "eagle-import") (part "CON_USB-C_RECEPTABLE_THT-SMD"))
    )
    (comp (ref "J20D")
      (value "ME813A-WH50C")
      (footprint "eagle-import:ME813A-WH50C")
      (libsource (lib "eagle-import") (part "ME813A-WH50C"))
    )
    (comp (ref "J21B")
      (value "CON_USB-C_RECEPTABLE_THT-SMD")
      (footprint "eagle-import:CON_USB-C_RECEPTABLE_THT-SMD")
      (libsource (lib "eagle-import") (part "CON_USB-C_RECEPTABLE_THT-SMD"))
    )
    (comp (ref "R12L")
      (value "1K")
      (footprint "eagle-import:RES0603@2")
      (libsource (lib "eagle-import") (part "00-own_parts_RES0603"))
    )
    (comp (ref "R13L")
      (value "1K")
      (footprint "eagle-import:RES0603@2")
      (libsource (lib "eagle-import") (part "00-own_parts_RES0603"))
    )
    (comp (ref "R20B")
      (value "120R")
      (footprint "eagle-import:RES0603@2")
      (libsource (lib "eagle-import") (part "00-own_parts_RES0603"))
    )
    (comp (ref "RX-BUS")
      (value "GRN")
      (footprint "eagle-import:LED_SMD_0603")
      (libsource (lib "eagle-import") (part "LED_SMD_0603"))
    )
    (comp (ref "TX-BUS")
      (value "RED")
      (footprint "eagle-import:LED_SMD_0603")
      (libsource (lib "eagle-import") (part "LED_SMD_0603"))
    )
    (comp (ref "U20")
      (value "ADM3485ARZ")
      (footprint "eagle-import:SO8")
      (libsource (lib "eagle-import") (part "ADM3485ARZ"))
    )
    (comp (ref "Z10U")
      (value "3V3")
      (footprint "eagle-import:ZENER_SOD80")
      (libsource (lib "eagle-import") (part "ZENER_SOD80"))
    )
    (comp (ref "Z11U")
      (value "3V3")
      (footprint "eagle-import:ZENER_SOD80")
      (libsource (lib "eagle-import") (part "ZENER_SOD80"))
    )
  )
  (nets
    (net (code "1") (name "BUS_A") (class "Default")
      (node (ref "J20B") (pin "A6") (pinfunction "A6.DP1_A6") (pintype "passive"))
      (node (ref "J21B") (pin "A6") (pinfunction "A6.DP1_A6") (pintype "passive"))
      (node (ref "R20B") (pin "1") (pinfunction "1_1") (pintype "passive"))
      (node (ref "U20") (pin "6") (pinfunction "6.A_6") (pintype "passive"))
      (node (ref "Z11U") (pin "2") (pinfunction "-_2") (pintype "passive"))
    )
    (net (code "2") (name "BUS_B") (class "Default")
      (node (ref "J20B") (pin "A7") (pinfunction "A7.DN1_A7") (pintype "passive"))
      (node (ref "J21B") (pin "A7") (pinfunction "A7.DN1_A7") (pintype "passive"))
      (node (ref "R20B") (pin "2") (pinfunction "2_2") (pintype "passive"))
      (node (ref "U20") (pin "7") (pinfunction "7.B_7") (pintype "passive"))
      (node (ref "Z10U") (pin "2") (pinfunction "-_2") (pintype "passive"))
    )
    (net (code "3") (name "CO2_RDY") (class "Default")
      (node (ref "U10") (pin "51") (pinfunction "51.PB12_51") (pintype "passive"))
      (node (ref "U60") (pin "5") (pinfunction "5.RDY_5") (pintype "passive"))
    )
    (net (code "4") (name "DIR_485") (class "Default")
      (node (ref "U10") (pin "25") (pinfunction "25.PA2_25") (pintype "passive"))
      (node (ref "U20") (pin "2") (pinfunction "2.~{RE}_2") (pintype "passive"))
      (node (ref "U20") (pin "3") (pinfunction "3.DE_3") (pintype "passive"))
    )
    (net (code "5") (name "EC0") (class "Default")
      (node (ref "R30F") (pin "2") (pinfunction "2_2") (pintype "passive"))
      (node (ref "U10") (pin "32") (pinfunction "32.PA7_32") (pintype "passive"))
      (node (ref "U30A") (pin "8") (pinfunction "7.OUT_8") (pintype "passive"))
    )
    (net (code "6") (name "EC0_DAC") (class "Default")
      (node (ref "R30B") (pin "2") (pinfunction "2_2") (pintype "passive"))
      (node (ref "R31B") (pin "1") (pinfunction "1_1") (pintype "passive"))
      (node (ref "U30A") (pin "3") (pinfunction "3.IN+_3") (pintype "passive"))
      (node (ref "U30M") (pin "4") (pinfunction "4.S3_4") (pintype "passive"))
    )
    (net (code "7") (name "EC0_IN") (class "Default")
      (node (ref "J30") (pin "3") (pinfunction "3_3") (pintype "passive"))
      (node (ref "R30F") (pin "1") (pinfunction "1_1") (pintype "passive"))
      (node (ref "U30A") (pin "7") (pinfunction "6.IN-_7") (pintype "passive"))
      (node (ref "Z31") (pin "2") (pinfunction "-_2") (pintype "passive"))
    )
    (net (code "8") (name "EC0_OUT") (class "Default")
      (node (ref "J30") (pin "4") (pinfunction "4_4") (pintype "passive"))
      (node (ref "R30O") (pin "1") (pinfunction "1_1") (pintype "passive"))
      (node (ref "Z32") (pin "2") (pinfunction "-_2") (pintype "passive"))
    )
    (net (code "9") (name "EC1") (class "Default")
      (node (ref "R31F") (pin "2") (pinfunction "2_2") (pintype "passive"))
      (node (ref "U10") (pin "26") (pinfunction "26.PA3_26") (pintype "passive"))
      (node (ref "U31A") (pin "8") (pinfunction "7.OUT_8") (pintype "passive"))
    )
    (net (code "10") (name "EC1_DAC") (class "Default")
      (node (ref "R32B") (pin "2") (pinfunction "2_2") (pintype "passive"))
      (node (ref "R33B") (pin "1") (pinfunction "1_1") (pintype "passive"))
      (node (ref "U30M") (pin "2") (pinfunction "2.S1_2") (pintype "passive"))
      (node (ref "U31A") (pin "3") (pinfunction "3.IN+_3") (pintype "passive"))
    )
    (net (code "11") (name "EC1_IN") (class "Default")
      (node (ref "J31") (pin "3") (pinfunction "3_3") (pintype "passive"))
      (node (ref "R31F") (pin "1") (pinfunction "1_1") (pintype "passive"))
      (node (ref "U31A") (pin "7") (pinfunction "6.IN-_7") (pintype "passive"))
      (node (ref "Z34") (pin "2") (pinfunction "-_2") (pintype "passive"))
    )
    (net (code "12") (name "EC1_OUT") (class "Default")
      (node (ref "J31") (pin "4") (pinfunction "4_4") (pintype "passive"))
      (node (ref "R31O") (pin "1") (pinfunction "1_1") (pintype "passive"))
      (node (ref "Z35") (pin "2") (pinfunction "-_2") (pintype "passive"))
    )
    (net (code "13") (name "EC2") (class "Default")
      (node (ref "R32F") (pin "2") (pinfunction "2_2") (pintype "passive"))
      (node (ref "U10") (pin "16") (pinfunction "16.PC1_16") (pintype "passive"))
      (node (ref "U32A") (pin "8") (pinfunction "7.OUT_8") (pintype "passive"))
    )
    (net (code "14") (name "EC2_DAC") (class "Default")
      (node (ref "R34B") (pin "2") (pinfunction "2_2") (pintype "passive"))
      (node (ref "R35B") (pin "1") (pinfunction "1_1") (pintype "passive"))
      (node (ref "U30M") (pin "7") (pinfunction "7.S4_7") (pintype "passive"))
      (node (ref "U32A") (pin "3") (pinfunction "3.IN+_3") (pintype "passive"))
    )
    (net (code "15") (name "EC2_IN") (class "Default")
      (node (ref "J32") (pin "3") (pinfunction "3_3") (pintype "passive"))
      (node (ref "R32F") (pin "1") (pinfunction "1_1") (pintype "passive"))
      (node (ref "U32A") (pin "7") (pinfunction "6.IN-_7") (pintype "passive"))
      (node (ref "Z37") (pin "2") (pinfunction "-_2") (pintype "passive"))
    )
    (net (code "16") (name "EC2_OUT") (class "Default")
      (node (ref "J32") (pin "4") (pinfunction "4_4") (pintype "passive"))
      (node (ref "R32O") (pin "1") (pinfunction "1_1") (pintype "passive"))
      (node (ref "Z38") (pin "2") (pinfunction "-_2") (pintype "passive"))
    )
    (net (code "17") (name "EC_DAC") (class "Default")
      (node (ref "U10") (pin "30") (pinfunction "30.PA5_30") (pintype "passive"))
      (node (ref "U30M") (pin "8") (pinfunction "8.D_8") (pintype "passive"))
    )
    (net (code "18") (name "EC_SEL0") (class "Default")
      (node (ref "U30M") (pin "1") (pinfunction "1.A0_1") (pintype "passive"))
    )
    (net (code "19") (name "EC_SEL1") (class "Default")
      (node (ref "U30M") (pin "10") (pinfunction "10.A1_10") (pintype "passive"))
    )
    (net (code "20") (name "GND") (class "Default")
      (node (ref "3V3") (pin "C") (pinfunction "C_C") (pintype "passive"))
      (node (ref "BAT10") (pin "2.-") (pinfunction "2_2.-") (pintype "passive"))
      (node (ref "C01I") (pin "2") (pinfunction "2_2") (pintype "passive"))
      (node (ref "C01O") (pin "2") (pinfunction "2_2") (pintype "passive"))
      (node (ref "C01S") (pin "2") (pinfunction "2_2") (pintype "passive"))
      (node (ref "C02I") (pin "2") (pinfunction "2_2") (pintype "passive"))
      (node (ref "C02O") (pin "2") (pinfunction "2_2") (pintype "passive"))
      (node (ref "C10") (pin "2") (pinfunction "2_2") (pintype "passive"))
      (node (ref "C10A") (pin "2") (pinfunction "2_2") (pintype "passive"))
      (node (ref "C10B") (pin "2") (pinfunction "2_2") (pintype "passive"))
      (node (ref "C10C") (pin "2") (pinfunction "2_2") (pintype "passive"))
      (node (ref "C10D") (pin "2") (pinfunction "2_2") (pintype "passive"))
      (node (ref "C10R") (pin "2") (pinfunction "2_2") (pintype "passive"))
      (node (ref "C10V") (pin "2") (pinfunction "2_2") (pintype "passive"))
      (node (ref "C11D") (pin "2") (pinfunction "2_2") (pintype "passive"))
      (node (ref "C11R") (pin "2") (pinfunction "2_2") (pintype "passive"))
      (node (ref "C11V") (pin "2") (pinfunction "2_2") (pintype "passive"))
      (node (ref "C12D") (pin "2") (pinfunction "2_2") (pintype "passive"))
      (node (ref "C12R") (pin "1") (pinfunction "1_1") (pintype "passive"))
      (node (ref "C13D") (pin "2") (pinfunction "2_2") (pintype "passive"))
      (node (ref "C14D") (pin "2") (pinfunction "2_2") (pintype "passive"))
      (node (ref "C15D") (pin "2") (pinfunction "2_2") (pintype "passive"))
      (node (ref "C20D") (pin "2") (pinfunction "2_2") (pintype "passive"))
      (node (ref "C21D") (pin "2") (pinfunction "2_2") (pintype "passive"))
      (node (ref "C30A") (pin "2") (pinfunction "2_2") (pintype "passive"))
      (node (ref "C30I") (pin "1") (pinfunction "1_1") (pintype "passive"))
      (node (ref "C30I1") (pin "1") (pinfunction "1_1") (pintype "passive"))
      (node (ref "C30I2") (pin "1") (pinfunction "1_1") (pintype "passive"))
      (node (ref "C30M") (pin "2") (pinfunction "2_2") (pintype "passive"))
      (node (ref "C30R") (pin "2") (pinfunction "2_2") (pintype "passive"))
      (node (ref "C31A") (pin "2") (pinfunction "2_2") (pintype "passive"))
      (node (ref "C31R") (pin "2") (pinfunction "2_2") (pintype "passive"))
      (node (ref "C32A") (pin "2") (pinfunction "2_2") (pintype "passive"))
      (node (ref "C40A") (pin "1") (pinfunction "1_1") (pintype "passive"))
      (node (ref "C40B") (pin "1") (pinfunction "1_1") (pintype "passive"))
      (node (ref "C40R") (pin "2") (pinfunction "2_2") (pintype "passive"))
      (node (ref "C41A") (pin "1") (pinfunction "1_1") (pintype "passive"))
      (node (ref "C41B") (pin "1") (pinfunction "1_1") (pintype "passive"))
      (node (ref "C41R") (pin "2") (pinfunction "2_2") (pintype "passive"))
      (node (ref "C42A") (pin "1") (pinfunction "1_1") (pintype "passive"))
      (node (ref "C42B") (pin "1") (pinfunction "1_1") (pintype "passive"))
      (node (ref "C60D") (pin "2") (pinfunction "2_2") (pintype "passive"))
      (node (ref "C61D") (pin "2") (pinfunction "2_2") (pintype "passive"))
      (node (ref "J10P") (pin "3") (pinfunction "3_3") (pintype "passive"))
      (node (ref "J10S") (pin "3") (pinfunction "3_3") (pintype "passive"))
      (node (ref "J20B") (pin "A1") (pinfunction "A1.GND_A1") (pintype "passive"))
      (node (ref "J20B") (pin "A11") (pinfunction "A11.NU_A11") (pintype "passive"))
      (node (ref "J20B") (pin "A12") (pinfunction "A12.GND_A12") (pintype "passive"))
      (node (ref "J20B") (pin "A2") (pinfunction "A2.NU_A2") (pintype "passive"))
      (node (ref "J20B") (pin "B1") (pinfunction "B1.GND_B1") (pintype "passive"))
      (node (ref "J20B") (pin "B11") (pinfunction "B11.NU_B11") (pintype "passive"))
      (node (ref "J20B") (pin "B12") (pinfunction "B12.GND_B12") (pintype "passive"))
      (node (ref "J20B") (pin "B2") (pinfunction "B2.NU_B2") (pintype "passive"))
      (node (ref "J20D") (pin "11") (pinfunction "11.GND_11") (pintype "passive"))
      (node (ref "J20D") (pin "12") (pinfunction "12.GND_12") (pintype "passive"))
      (node (ref "J21B") (pin "A1") (pinfunction "A1.GND_A1") (pintype "passive"))
      (node (ref "J21B") (pin "A11") (pinfunction "A11.NU_A11") (pintype "passive"))
      (node (ref "J21B") (pin "A12") (pinfunction "A12.GND_A12") (pintype "passive"))
      (node (ref "J21B") (pin "A2") (pinfunction "A2.NU_A2") (pintype "passive"))
      (node (ref "J21B") (pin "B1") (pinfunction "B1.GND_B1") (pintype "passive"))
      (node (ref "J21B") (pin "B11") (pinfunction "B11.NU_B11") (pintype "passive"))
      (node (ref "J21B") (pin "B12") (pinfunction "B12.GND_B12") (pintype "passive"))
      (node (ref "J21B") (pin "B2") (pinfunction "B2.NU_B2") (pintype "passive"))
      (node (ref "J30") (pin "2") (pinfunction "2_2") (pintype "passive"))
      (node (ref "J31") (pin "2") (pinfunction "2_2") (pintype "passive"))
      (node (ref "J32") (pin "2") (pinfunction "2_2") (pintype "passive"))
      (node (ref "J60") (pin "2") (pinfunction "2_2") (pintype "passive"))
      (node (ref "LD10-R") (pin "C") (pinfunction "C_C") (pintype "passive"))
      (node (ref "LD11-G") (pin "C") (pinfunction "C_C") (pintype "passive"))
      (node (ref "LD50R") (pin "C") (pinfunction "C_C") (pintype "passive"))
      (node (ref "LD51R") (pin "C") (pinfunction "C_C") (pintype "passive"))
      (node (ref "LD52R") (pin "C") (pinfunction "C_C") (pintype "passive"))
      (node (ref "R02F") (pin "1") (pinfunction "1_1") (pintype "passive"))
      (node (ref "R31B") (pin "2") (pinfunction "2_2") (pintype "passive"))
      (node (ref "R31I") (pin "2") (pinfunction "2_2") (pintype "passive"))
      (node (ref "R33B") (pin "2") (pinfunction "2_2") (pintype "passive"))
      (node (ref "R33I") (pin "2") (pinfunction "2_2") (pintype "passive"))
      (node (ref "R35B") (pin "2") (pinfunction "2_2") (pintype "passive"))
      (node (ref "R35I") (pin "2") (pinfunction "2_2") (pintype "passive"))
      (node (ref "R41B") (pin "2") (pinfunction "2_2") (pintype "passive"))
      (node (ref "R43B") (pin "2") (pinfunction "2_2") (pintype "passive"))
      (node (ref "R45B") (pin "2") (pinfunction "2_2") (pintype "passive"))
      (node (ref "R51S") (pin "2") (pinfunction "2_2") (pintype "passive"))
      (node (ref "R53S") (pin "2") (pinfunction "2_2") (pintype "passive"))
      (node (ref "R55S") (pin "2") (pinfunction "2_2") (pintype "passive"))
      (node (ref "R60L") (pin "2") (pinfunction "2_2") (pintype "passive"))
      (node (ref "RESET") (pin "1") (pinfunction "1-2_1") (pintype "passive"))
      (node (ref "T50P") (pin "2") (pinfunction "S2_2") (pintype "bidirectional"))
      (node (ref "T51P") (pin "2") (pinfunction "S2_2") (pintype "bidirectional"))
      (node (ref "T52P") (pin "2") (pinfunction "S2_2") (pintype "bidirectional"))
      (node (ref "TP2") (pin "1") (pinfunction "P$1_1") (pintype "passive"))
      (node (ref "U01") (pin "2") (pinfunction "2.SYNC_2") (pintype "passive"))
      (node (ref "U01") (pin "4") (pinfunction "4.GND_4") (pintype "passive"))
      (node (ref "U01") (pin "TP") (pinfunction "TP_TP") (pintype "passive"))
      (node (ref "U10") (pin "10") (pinfunction "10.VSS_10") (pintype "passive"))
      (node (ref "U10") (pin "20") (pinfunction "20.VSSA_20") (pintype "passive"))
      (node (ref "U10") (pin "27") (pinfunction "27.VSS_27") (pintype "passive"))
      (node (ref "U10") (pin "74") (pinfunction "74.VSS_74") (pintype "passive"))
      (node (ref "U10") (pin "94") (pinfunction "94.BOOT0_94") (pintype "passive"))
      (node (ref "U10") (pin "99") (pinfunction "99.VSS_99") (pintype "passive"))
      (node (ref "U10R") (pin "2") (pinfunction "2.GND_2") (pintype "passive"))
      (node (ref "U11") (pin "10") (pinfunction "15.GND_10") (pintype "passive"))
      (node (ref "U11") (pin "11") (pinfunction "15.GND_11") (pintype "passive"))
      (node (ref "U11") (pin "12") (pinfunction "15.GND_12") (pintype "passive"))
      (node (ref "U11") (pin "13") (pinfunction "15.GND_13") (pintype "passive"))
      (node (ref "U11") (pin "14") (pinfunction "15.GND_14") (pintype "passive"))
      (node (ref "U11") (pin "15") (pinfunction "15.GND_15") (pintype "passive"))
      (node (ref "U11") (pin "2") (pinfunction "15.GND_2") (pintype "passive"))
      (node (ref "U11") (pin "7") (pinfunction "15.GND_7") (pintype "passive"))
      (node (ref "U11") (pin "8") (pinfunction "15.GND_8") (pintype "passive"))
      (node (ref "U11") (pin "9") (pinfunction "15.GND_9") (pintype "passive"))
      (node (ref "U20") (pin "5") (pinfunction "5.GND_5") (pintype "passive"))
      (node (ref "U30A") (pin "4") (pinfunction "4.V-_4") (pintype "passive"))
      (node (ref "U30M") (pin "3") (pinfunction "3.GND_3") (pintype "passive"))
      (node (ref "U30R") (pin "2") (pinfunction "2.GND_2") (pintype "passive"))
      (node (ref "U31A") (pin "4") (pinfunction "4.V-_4") (pintype "passive"))
      (node (ref "U32A") (pin "4") (pinfunction "4.V-_4") (pintype "passive"))
      (node (ref "U40A") (pin "4") (pinfunction "4.V-_4") (pintype "passive"))
      (node (ref "U40R") (pin "2") (pinfunction "2.GND_2") (pintype "passive"))
      (node (ref "U41A") (pin "4") (pinfunction "4.V-_4") (pintype "passive"))
      (node (ref "U42A") (pin "4") (pinfunction "4.V-_4") (pintype "passive"))
      (node (ref "U60") (pin "2") (pinfunction "2.GND_2") (pintype "passive"))
      (node (ref "U61") (pin "1") (pinfunction "1.GND_1") (pintype "passive"))
      (node (ref "VIN") (pin "C") (pinfunction "C_C") (pintype "passive"))
      (node (ref "Z10P") (pin "1") (pinfunction "+_1") (pintype "passive"))
      (node (ref "Z10S") (pin "1") (pinfunction "+_1") (pintype "passive"))
      (node (ref "Z10U") (pin "1") (pinfunction "+_1") (pintype "passive"))
      (node (ref "Z112P") (pin "1") (pinfunction "+_1") (pintype "passive"))
      (node (ref "Z11S") (pin "1") (pinfunction "+_1") (pintype "passive"))
      (node (ref "Z11U") (pin "1") (pinfunction "+_1") (pintype "passive"))
      (node (ref "Z30") (pin "1") (pinfunction "+_1") (pintype "passive"))
      (node (ref "Z31") (pin "1") (pinfunction "+_1") (pintype "passive"))
      (node (ref "Z32") (pin "1") (pinfunction "+_1") (pintype "passive"))
      (node (ref "Z33") (pin "1") (pinfunction "+_1") (pintype "passive"))
      (node (ref "Z34") (pin "1") (pinfunction "+_1") (pintype "passive"))
      (node (ref "Z35") (pin "1") (pinfunction "+_1") (pintype "passive"))
      (node (ref "Z36") (pin "1") (pinfunction "+_1") (pintype "passive"))
      (node (ref "Z37") (pin "1") (pinfunction "+_1") (pintype "passive"))
      (node (ref "Z38") (pin "1") (pinfunction "+_1") (pintype "passive"))
      (node (ref "Z50") (pin "1") (pinfunction "+_1") (pintype "passive"))
      (node (ref "Z51") (pin "1") (pinfunction "+_1") (pintype "passive"))
      (node (ref "Z52") (pin "1") (pinfunction "+_1") (pintype "passive"))
      (node (ref "Z53") (pin "1") (pinfunction "+_1") (pintype "passive"))
      (node (ref "Z54") (pin "1") (pinfunction "+_1") (pintype "passive"))
      (node (ref "Z55") (pin "1") (pinfunction "+_1") (pintype "passive"))
      (node (ref "Z56") (pin "1") (pinfunction "+_1") (pintype "passive"))
      (node (ref "Z57") (pin "1") (pinfunction "+_1") (pintype "passive"))
      (node (ref "Z58") (pin "1") (pinfunction "+_1") (pintype "passive"))
      (node (ref "Z59") (pin "1") (pinfunction "+_1") (pintype "passive"))
      (node (ref "Z5A") (pin "1") (pinfunction "+_1") (pintype "passive"))
      (node (ref "Z5B") (pin "1") (pinfunction "+_1") (pintype "passive"))
      (node (ref "Z60") (pin "1") (pinfunction "+_1") (pintype "passive"))
    )
    (net (code "21") (name "LED_GRN") (class "Default")
      (node (ref "GRN") (pin "1") (pinfunction "P$1_1") (pintype "passive"))
      (node (ref "R11L") (pin "1") (pinfunction "1_1") (pintype "passive"))
      (node (ref "U10") (pin "93") (pinfunction "93.PB7_93") (pintype "passive"))
    )
    (net (code "22") (name "LED_RED") (class "Default")
      (node (ref "R10L") (pin "1") (pinfunction "1_1") (pintype "passive"))
      (node (ref "RED") (pin "1") (pinfunction "P$1_1") (pintype "passive"))
      (node (ref "U10") (pin "92") (pinfunction "92.PB6_92") (pintype "passive"))
    )
    (net (code "23") (name "LEVEL0") (class "Default")
      (node (ref "J50") (pin "3") (pinfunction "3_3") (pintype "passive"))
      (node (ref "U10") (pin "3") (pinfunction "3.PE4_3") (pintype "passive"))
      (node (ref "Z52") (pin "2") (pinfunction "-_2") (pintype "passive"))
    )
    (net (code "24") (name "LEVEL1") (class "Default")
      (node (ref "J51") (pin "3") (pinfunction "3_3") (pintype "passive"))
      (node (ref "U10") (pin "98") (pinfunction "98.PE1_98") (pintype "passive"))
      (node (ref "Z56") (pin "2") (pinfunction "-_2") (pintype "passive"))
    )
    (net (code "25") (name "LEVEL2") (class "Default")
      (node (ref "J52") (pin "3") (pinfunction "3_3") (pintype "passive"))
      (node (ref "U10") (pin "95") (pinfunction "95.PB8_95") (pintype "passive"))
      (node (ref "Z5A") (pin "2") (pinfunction "-_2") (pintype "passive"))
    )
    (net (code "26") (name "LIGHT_OUT") (class "Default")
      (node (ref "R60L") (pin "1") (pinfunction "1_1") (pintype "passive"))
      (node (ref "U10") (pin "36") (pinfunction "36.PB1_36") (pintype "passive"))
      (node (ref "U61") (pin "3") (pinfunction "3.IOUT_3") (pintype "passive"))
    )
    (net (code "27") (name "LIGHT_SD") (class "Default")
      (node (ref "U10") (pin "35") (pinfunction "35.PB0_35") (pintype "passive"))
      (node (ref "U61") (pin "6") (pinfunction "6.SD_6") (pintype "passive"))
    )
    (net (code "28") (name "MISO0") (class "Default")
      (node (ref "J20D") (pin "3") (pinfunction "3.MISO_3") (pintype "passive"))
      (node (ref "U10") (pin "79") (pinfunction "79.PC11_79") (pintype "passive"))
      (node (ref "U11") (pin "19") (pinfunction "19.DOUT_19") (pintype "passive"))
    )
    (net (code "29") (name "MOSI0") (class "Default")
      (node (ref "J20D") (pin "4") (pinfunction "4.MOSI_4") (pintype "passive"))
      (node (ref "U10") (pin "80") (pinfunction "80.PC12_80") (pintype "passive"))
      (node (ref "U11") (pin "17") (pinfunction "17.DIN_17") (pintype "passive"))
    )
    (net (code "30") (name "NTC0") (class "Default")
      (node (ref "J30") (pin "1") (pinfunction "1_1") (pintype "passive"))
      (node (ref "R30C") (pin "2") (pinfunction "2_2") (pintype "passive"))
      (node (ref "U10") (pin "33") (pinfunction "33.PC4_33") (pintype "passive"))
      (node (ref "Z30") (pin "2") (pinfunction "-_2") (pintype "passive"))
    )
    (net (code "31") (name "NTC1") (class "Default")
      (node (ref "J31") (pin "1") (pinfunction "1_1") (pintype "passive"))
      (node (ref "R31C") (pin "2") (pinfunction "2_2") (pintype "passive"))
      (node (ref "U10") (pin "29") (pinfunction "29.PA4_29") (pintype "passive"))
      (node (ref "Z33") (pin "2") (pinfunction "-_2") (pintype "passive"))
    )
    (net (code "32") (name "NTC2") (class "Default")
      (node (ref "J32") (pin "1") (pinfunction "1_1") (pintype "passive"))
      (node (ref "R32C") (pin "2") (pinfunction "2_2") (pintype "passive"))
      (node (ref "U10") (pin "17") (pinfunction "17.PC2_17") (pintype "passive"))
      (node (ref "Z36") (pin "2") (pinfunction "-_2") (pintype "passive"))
    )
    (net (code "33") (name "Net-(3V3-PadA)") (class "Default")
      (node (ref "3V3") (pin "A") (pinfunction "A_A") (pintype "passive"))
      (node (ref "R02L") (pin "2") (pinfunction "2_2") (pintype "passive"))
    )
    (net (code "34") (name "Net-(LD10-R-PadA)") (class "Default")
      (node (ref "LD10-R") (pin "A") (pinfunction "A_A") (pintype "passive"))
      (node (ref "R10L") (pin "2") (pinfunction "2_2") (pintype "passive"))
    )
    (net (code "35") (name "Net-(LD11-G-PadA)") (class "Default")
      (node (ref "LD11-G") (pin "A") (pinfunction "A_A") (pintype "passive"))
      (node (ref "R11L") (pin "2") (pinfunction "2_2") (pintype "passive"))
    )
    (net (code "36") (name "Net-(LD50R-PadA)") (class "Default")
      (node (ref "LD50R") (pin "A") (pinfunction "A_A") (pintype "passive"))
      (node (ref "R50L") (pin "2") (pinfunction "2_2") (pintype "passive"))
    )
    (net (code "37") (name "Net-(LD51R-PadA)") (class "Default")
      (node (ref "LD51R") (pin "A") (pinfunction "A_A") (pintype "passive"))
      (node (ref "R51L") (pin "2") (pinfunction "2_2") (pintype "passive"))
    )
    (net (code "38") (name "Net-(LD52R-PadA)") (class "Default")
      (node (ref "LD52R") (pin "A") (pinfunction "A_A") (pintype "passive"))
      (node (ref "R52L") (pin "2") (pinfunction "2_2") (pintype "passive"))
    )
    (net (code "39") (name "Net-(R01L-Pad2)") (class "Default")
      (node (ref "R01L") (pin "2") (pinfunction "2_2") (pintype "passive"))
      (node (ref "VIN") (pin "A") (pinfunction "A_A") (pintype "passive"))
    )
    (net (code "40") (name "Net-(R12L-Pad2)") (class "Default")
      (node (ref "R12L") (pin "2") (pinfunction "2_2") (pintype "passive"))
      (node (ref "TX-BUS") (pin "A") (pinfunction "A_A") (pintype "passive"))
    )
    (net (code "41") (name "Net-(R13L-Pad2)") (class "Default")
      (node (ref "R13L") (pin "2") (pinfunction "2_2") (pintype "passive"))
      (node (ref "RX-BUS") (pin "A") (pinfunction "A_A") (pintype "passive"))
    )
    (net (code "42") (name "Net-(T50P-D3)") (class "Default")
      (node (ref "J50") (pin "4") (pinfunction "4_4") (pintype "passive"))
      (node (ref "T50P") (pin "3") (pinfunction "D3_3") (pintype "bidirectional"))
      (node (ref "Z53") (pin "2") (pinfunction "-_2") (pintype "passive"))
    )
    (net (code "43") (name "Net-(T51P-D3)") (class "Default")
      (node (ref "J51") (pin "4") (pinfunction "4_4") (pintype "passive"))
      (node (ref "T51P") (pin "3") (pinfunction "D3_3") (pintype "bidirectional"))
      (node (ref "Z57") (pin "2") (pinfunction "-_2") (pintype "passive"))
    )
    (net (code "44") (name "Net-(T52P-D3)") (class "Default")
      (node (ref "J52") (pin "4") (pinfunction "4_4") (pintype "passive"))
      (node (ref "T52P") (pin "3") (pinfunction "D3_3") (pintype "bidirectional"))
      (node (ref "Z5B") (pin "2") (pinfunction "-_2") (pintype "passive"))
    )
    (net (code "45") (name "Net-(U01-5.FB)") (class "Default")
      (node (ref "R01F") (pin "1") (pinfunction "1_1") (pintype "passive"))
      (node (ref "R02F") (pin "2") (pinfunction "2_2") (pintype "passive"))
      (node (ref "U01") (pin "5") (pinfunction "5.FB_5") (pintype "passive"))
    )
    (net (code "46") (name "Net-(U01-6.SS)") (class "Default")
      (node (ref "C01S") (pin "1") (pinfunction "1_1") (pintype "passive"))
      (node (ref "U01") (pin "6") (pinfunction "6.SS_6") (pintype "passive"))
    )
    (net (code "47") (name "Net-(U10-21.VREF+)") (class "Default")
      (node (ref "C12R") (pin "2") (pinfunction "2_2") (pintype "passive"))
      (node (ref "L10R") (pin "2") (pinfunction "2_2") (pintype "passive"))
      (node (ref "U10") (pin "21") (pinfunction "21.VREF+_21") (pintype "passive"))
    )
    (net (code "48") (name "Net-(U10-49.VCAP1)") (class "Default")
      (node (ref "C10V") (pin "1") (pinfunction "1_1") (pintype "passive"))
      (node (ref "U10") (pin "49") (pinfunction "49.VCAP1_49") (pintype "passive"))
    )
    (net (code "49") (name "Net-(U10-73.VCAP2)") (class "Default")
      (node (ref "C11V") (pin "1") (pinfunction "1_1") (pintype "passive"))
      (node (ref "U10") (pin "73") (pinfunction "73.VCAP2_73") (pintype "passive"))
    )
    (net (code "50") (name "Net-(U30AA-1.OUT)") (class "Default")
      (node (ref "R30O") (pin "2") (pinfunction "2_2") (pintype "passive"))
      (node (ref "U30A") (pin "1") (pinfunction "1.OUT_1") (pintype "passive"))
      (node (ref "U30A") (pin "2") (pinfunction "2.IN-_2") (pintype "passive"))
    )
    (net (code "51") (name "Net-(U30AB-5.IN+)") (class "Default")
      (node (ref "C30I") (pin "2") (pinfunction "2_2") (pintype "passive"))
      (node (ref "R30I") (pin "2") (pinfunction "2_2") (pintype "passive"))
      (node (ref "R31I") (pin "1") (pinfunction "1_1") (pintype "passive"))
      (node (ref "U30A") (pin "6") (pinfunction "5.IN+_6") (pintype "passive"))
    )
    (net (code "52") (name "Net-(U31AA-1.OUT)") (class "Default")
      (node (ref "R31O") (pin "2") (pinfunction "2_2") (pintype "passive"))
      (node (ref "U31A") (pin "1") (pinfunction "1.OUT_1") (pintype "passive"))
      (node (ref "U31A") (pin "2") (pinfunction "2.IN-_2") (pintype "passive"))
    )
    (net (code "53") (name "Net-(U31AB-5.IN+)") (class "Default")
      (node (ref "C30I1") (pin "2") (pinfunction "2_2") (pintype "passive"))
      (node (ref "R32I") (pin "2") (pinfunction "2_2") (pintype "passive"))
      (node (ref "R33I") (pin "1") (pinfunction "1_1") (pintype "passive"))
      (node (ref "U31A") (pin "6") (pinfunction "5.IN+_6") (pintype "passive"))
    )
    (net (code "54") (name "Net-(U32AA-1.OUT)") (class "Default")
      (node (ref "R32O") (pin "2") (pinfunction "2_2") (pintype "passive"))
      (node (ref "U32A") (pin "1") (pinfunction "1.OUT_1") (pintype "passive"))
      (node (ref "U32A") (pin "2") (pinfunction "2.IN-_2") (pintype "passive"))
    )
    (net (code "55") (name "Net-(U32AB-5.IN+)") (class "Default")
      (node (ref "C30I2") (pin "2") (pinfunction "2_2") (pintype "passive"))
      (node (ref "R34I") (pin "2") (pinfunction "2_2") (pintype "passive"))
      (node (ref "R35I") (pin "1") (pinfunction "1_1") (pintype "passive"))
      (node (ref "U32A") (pin "6") (pinfunction "5.IN+_6") (pintype "passive"))
    )
    (net (code "56") (name "Net-(U40AB-5.IN+)") (class "Default")
      (node (ref "R40I") (pin "2") (pinfunction "2_2") (pintype "passive"))
      (node (ref "U40A") (pin "6") (pinfunction "5.IN+_6") (pintype "passive"))
    )
    (net (code "57") (name "Net-(U41AB-5.IN+)") (class "Default")
      (node (ref "R41I") (pin "2") (pinfunction "2_2") (pintype "passive"))
      (node (ref "U41A") (pin "6") (pinfunction "5.IN+_6") (pintype "passive"))
    )
    (net (code "58") (name "Net-(U42AB-5.IN+)") (class "Default")
      (node (ref "R42I") (pin "2") (pinfunction "2_2") (pintype "passive"))
      (node (ref "U42A") (pin "6") (pinfunction "5.IN+_6") (pintype "passive"))
    )
    (net (code "59") (name "Net-(Z50--)") (class "Default")
      (node (ref "J50") (pin "1") (pinfunction "1_1") (pintype "passive"))
      (node (ref "R50P") (pin "2") (pinfunction "2_2") (pintype "passive"))
      (node (ref "Z50") (pin "2") (pinfunction "-_2") (pintype "passive"))
    )
    (net (code "60") (name "Net-(Z51--)") (class "Default")
      (node (ref "J50") (pin "2") (pinfunction "2_2") (pintype "passive"))
      (node (ref "R50S") (pin "2") (pinfunction "2_2") (pintype "passive"))
      (node (ref "R51S") (pin "1") (pinfunction "1_1") (pintype "passive"))
      (node (ref "Z51") (pin "2") (pinfunction "-_2") (pintype "passive"))
    )
    (net (code "61") (name "Net-(Z54--)") (class "Default")
      (node (ref "J51") (pin "1") (pinfunction "1_1") (pintype "passive"))
      (node (ref "R51P") (pin "2") (pinfunction "2_2") (pintype "passive"))
      (node (ref "Z54") (pin "2") (pinfunction "-_2") (pintype "passive"))
    )
    (net (code "62") (name "Net-(Z55--)") (class "Default")
      (node (ref "J51") (pin "2") (pinfunction "2_2") (pintype "passive"))
      (node (ref "R52S") (pin "2") (pinfunction "2_2") (pintype "passive"))
      (node (ref "R53S") (pin "1") (pinfunction "1_1") (pintype "passive"))
      (node (ref "Z55") (pin "2") (pinfunction "-_2") (pintype "passive"))
    )
    (net (code "63") (name "Net-(Z58--)") (class "Default")
      (node (ref "J52") (pin "1") (pinfunction "1_1") (pintype "passive"))
      (node (ref "R52P") (pin "2") (pinfunction "2_2") (pintype "passive"))
      (node (ref "Z58") (pin "2") (pinfunction "-_2") (pintype "passive"))
    )
    (net (code "64") (name "Net-(Z59--)") (class "Default")
      (node (ref "J52") (pin "2") (pinfunction "2_2") (pintype "passive"))
      (node (ref "R54S") (pin "2") (pinfunction "2_2") (pintype "passive"))
      (node (ref "R55S") (pin "1") (pinfunction "1_1") (pintype "passive"))
      (node (ref "Z59") (pin "2") (pinfunction "-_2") (pintype "passive"))
    )
    (net (code "65") (name "PAR_OUT") (class "Default")
      (node (ref "J60") (pin "1") (pinfunction "1_1") (pintype "passive"))
      (node (ref "U10") (pin "15") (pinfunction "15.PC0_15") (pintype "passive"))
      (node (ref "Z60") (pin "2") (pinfunction "-_2") (pintype "passive"))
    )
    (net (code "66") (name "PH0") (class "Default")
      (node (ref "U10") (pin "34") (pinfunction "34.PC5_34") (pintype "passive"))
      (node (ref "U40A") (pin "7") (pinfunction "6.IN-_7") (pintype "passive"))
      (node (ref "U40A") (pin "8") (pinfunction "7.OUT_8") (pintype "passive"))
    )
    (net (code "67") (name "PH0_IN") (class "Default")
      (node (ref "J40") (pin "PIN") (pinfunction "1_PIN") (pintype "passive"))
      (node (ref "R40I") (pin "1") (pinfunction "1_1") (pintype "passive"))
    )
    (net (code "68") (name "PH1") (class "Default")
      (node (ref "U10") (pin "31") (pinfunction "31.PA6_31") (pintype "passive"))
      (node (ref "U41A") (pin "7") (pinfunction "6.IN-_7") (pintype "passive"))
      (node (ref "U41A") (pin "8") (pinfunction "7.OUT_8") (pintype "passive"))
    )
    (net (code "69") (name "PH1_IN") (class "Default")
      (node (ref "J41") (pin "PIN") (pinfunction "1_PIN") (pintype "passive"))
      (node (ref "R41I") (pin "1") (pinfunction "1_1") (pintype "passive"))
    )
    (net (code "70") (name "PH2") (class "Default")
      (node (ref "U10") (pin "18") (pinfunction "18.PC3_18") (pintype "passive"))
      (node (ref "U42A") (pin "7") (pinfunction "6.IN-_7") (pintype "passive"))
      (node (ref "U42A") (pin "8") (pinfunction "7.OUT_8") (pintype "passive"))
    )
    (net (code "71") (name "PH2_IN") (class "Default")
      (node (ref "J42") (pin "PIN") (pinfunction "1_PIN") (pintype "passive"))
      (node (ref "R42I") (pin "1") (pinfunction "1_1") (pintype "passive"))
    )
    (net (code "72") (name "PUMP0") (class "Default")
      (node (ref "R50L") (pin "1") (pinfunction "1_1") (pintype "passive"))
      (node (ref "T50P") (pin "1") (pinfunction "G1_1") (pintype "bidirectional"))
      (node (ref "U10") (pin "4") (pinfunction "4.PE5_4") (pintype "passive"))
    )
    (net (code "73") (name "PUMP1") (class "Default")
      (node (ref "R51L") (pin "1") (pinfunction "1_1") (pintype "passive"))
      (node (ref "T51P") (pin "1") (pinfunction "G1_1") (pintype "bidirectional"))
      (node (ref "U10") (pin "1") (pinfunction "1.PE2_1") (pintype "passive"))
    )
    (net (code "74") (name "PUMP2") (class "Default")
      (node (ref "R52L") (pin "1") (pinfunction "1_1") (pintype "passive"))
      (node (ref "T52P") (pin "1") (pinfunction "G1_1") (pintype "bidirectional"))
      (node (ref "U10") (pin "96") (pinfunction "96.PB9_96") (pintype "passive"))
    )
    (net (code "75") (name "REF_EC") (class "Default")
      (node (ref "U10") (pin "38") (pinfunction "38.PE7_38") (pintype "passive"))
      (node (ref "U30R") (pin "3") (pinfunction "3.ENA_3") (pintype "passive"))
    )
    (net (code "76") (name "REF_PH") (class "Default")
      (node (ref "U10") (pin "39") (pinfunction "39.PE8_39") (pintype "passive"))
      (node (ref "U40R") (pin "3") (pinfunction "3.ENA_3") (pintype "passive"))
    )
    (net (code "77") (name "RXD_232") (class "Default")
      (node (ref "J10S") (pin "1") (pinfunction "1_1") (pintype "passive"))
      (node (ref "U10") (pin "69") (pinfunction "69.PA10_69") (pintype "passive"))
      (node (ref "Z11S") (pin "2") (pinfunction "-_2") (pintype "passive"))
    )
    (net (code "78") (name "RXD_485") (class "Default")
      (node (ref "RX-BUS") (pin "C") (pinfunction "C_C") (pintype "passive"))
      (node (ref "U10") (pin "24") (pinfunction "24.PA1_24") (pintype "passive"))
      (node (ref "U20") (pin "1") (pinfunction "1.RO_1") (pintype "passive"))
    )
    (net (code "79") (name "SCK0") (class "Default")
      (node (ref "J20D") (pin "1") (pinfunction "1.SCK_1") (pintype "passive"))
      (node (ref "U10") (pin "78") (pinfunction "78.PC10_78") (pintype "passive"))
      (node (ref "U11") (pin "18") (pinfunction "18/20.SCLK_18") (pintype "passive"))
      (node (ref "U11") (pin "20") (pinfunction "18/20.SCLK_20") (pintype "passive"))
    )
    (net (code "80") (name "SCL0") (class "Default")
      (node (ref "R10I") (pin "2") (pinfunction "2_2") (pintype "passive"))
      (node (ref "U10") (pin "47") (pinfunction "47.PB10_47") (pintype "passive"))
      (node (ref "U60") (pin "3") (pinfunction "3.SCL_3") (pintype "passive"))
    )
    (net (code "81") (name "SDA0") (class "Default")
      (node (ref "R11I") (pin "2") (pinfunction "2_2") (pintype "passive"))
      (node (ref "U10") (pin "48") (pinfunction "48.PB11_48") (pintype "passive"))
      (node (ref "U60") (pin "4") (pinfunction "4.SDA_4") (pintype "passive"))
    )
    (net (code "82") (name "SWCLK") (class "Default")
      (node (ref "J10P") (pin "2") (pinfunction "2_2") (pintype "passive"))
      (node (ref "U10") (pin "76") (pinfunction "76.PA14_76") (pintype "passive"))
      (node (ref "Z112P") (pin "2") (pinfunction "-_2") (pintype "passive"))
    )
    (net (code "83") (name "SWDIO") (class "Default")
      (node (ref "J10P") (pin "1") (pinfunction "1_1") (pintype "passive"))
      (node (ref "U10") (pin "72") (pinfunction "72.PA13_72") (pintype "passive"))
      (node (ref "Z10P") (pin "2") (pinfunction "-_2") (pintype "passive"))
    )
    (net (code "84") (name "TXD_232") (class "Default")
      (node (ref "J10S") (pin "2") (pinfunction "2_2") (pintype "passive"))
      (node (ref "U10") (pin "68") (pinfunction "68.PA9_68") (pintype "passive"))
      (node (ref "Z10S") (pin "2") (pinfunction "-_2") (pintype "passive"))
    )
    (net (code "85") (name "TXD_485") (class "Default")
      (node (ref "TX-BUS") (pin "C") (pinfunction "C_C") (pintype "passive"))
      (node (ref "U10") (pin "23") (pinfunction "23.PA0_23") (pintype "passive"))
      (node (ref "U20") (pin "4") (pinfunction "4.DI_4") (pintype "passive"))
    )
    (net (code "86") (name "V0") (class "Default")
      (node (ref "C30A") (pin "1") (pinfunction "1_1") (pintype "passive"))
      (node (ref "L30A") (pin "2") (pinfunction "2_2") (pintype "passive"))
      (node (ref "R30B") (pin "1") (pinfunction "1_1") (pintype "passive"))
      (node (ref "R30C") (pin "1") (pinfunction "1_1") (pintype "passive"))
      (node (ref "R30I") (pin "1") (pinfunction "1_1") (pintype "passive"))
      (node (ref "U30A") (pin "5") (pinfunction "8.V+_5") (pintype "passive"))
    )
    (net (code "87") (name "V1") (class "Default")
      (node (ref "C31A") (pin "1") (pinfunction "1_1") (pintype "passive"))
      (node (ref "L31A") (pin "2") (pinfunction "2_2") (pintype "passive"))
      (node (ref "R31C") (pin "1") (pinfunction "1_1") (pintype "passive"))
      (node (ref "R32B") (pin "1") (pinfunction "1_1") (pintype "passive"))
      (node (ref "R32I") (pin "1") (pinfunction "1_1") (pintype "passive"))
      (node (ref "U31A") (pin "5") (pinfunction "8.V+_5") (pintype "passive"))
    )
    (net (code "88") (name "V2") (class "Default")
      (node (ref "C32A") (pin "1") (pinfunction "1_1") (pintype "passive"))
      (node (ref "L32A") (pin "2") (pinfunction "2_2") (pintype "passive"))
      (node (ref "R32C") (pin "1") (pinfunction "1_1") (pintype "passive"))
      (node (ref "R34B") (pin "1") (pinfunction "1_1") (pintype "passive"))
      (node (ref "R34I") (pin "1") (pinfunction "1_1") (pintype "passive"))
      (node (ref "U32A") (pin "5") (pinfunction "8.V+_5") (pintype "passive"))
    )
    (net (code "89") (name "V3") (class "Default")
      (node (ref "C40A") (pin "2") (pinfunction "2_2") (pintype "passive"))
      (node (ref "L40A") (pin "2") (pinfunction "2_2") (pintype "passive"))
      (node (ref "R40B") (pin "1") (pinfunction "1_1") (pintype "passive"))
      (node (ref "U40A") (pin "5") (pinfunction "8.V+_5") (pintype "passive"))
    )
    (net (code "90") (name "V4") (class "Default")
      (node (ref "C41A") (pin "2") (pinfunction "2_2") (pintype "passive"))
      (node (ref "L41A") (pin "2") (pinfunction "2_2") (pintype "passive"))
      (node (ref "R42B") (pin "1") (pinfunction "1_1") (pintype "passive"))
      (node (ref "U41A") (pin "5") (pinfunction "8.V+_5") (pintype "passive"))
    )
    (net (code "91") (name "V5") (class "Default")
      (node (ref "C42A") (pin "2") (pinfunction "2_2") (pintype "passive"))
      (node (ref "L42A") (pin "2") (pinfunction "2_2") (pintype "passive"))
      (node (ref "R44B") (pin "1") (pinfunction "1_1") (pintype "passive"))
      (node (ref "U42A") (pin "5") (pinfunction "8.V+_5") (pintype "passive"))
    )
    (net (code "92") (name "VBAT") (class "Default")
      (node (ref "BAT10") (pin "1.+") (pinfunction "1_1.+") (pintype "passive"))
      (node (ref "U11") (pin "16") (pinfunction "16.VBAT_16") (pintype "passive"))
    )
    (net (code "93") (name "VBIAS0") (class "Default")
      (node (ref "J40") (pin "GND1") (pinfunction "GND_GND1") (pintype "passive"))
      (node (ref "J40") (pin "GND2") (pinfunction "GND_GND2") (pintype "passive"))
      (node (ref "J40") (pin "GND3") (pinfunction "GND_GND3") (pintype "passive"))
      (node (ref "J40") (pin "GND4") (pinfunction "GND_GND4") (pintype "passive"))
      (node (ref "J40") (pin "GND5") (pinfunction "GND_GND5") (pintype "passive"))
      (node (ref "U40A") (pin "1") (pinfunction "1.OUT_1") (pintype "passive"))
      (node (ref "U40A") (pin "2") (pinfunction "2.IN-_2") (pintype "passive"))
    )
    (net (code "94") (name "VBIAS1") (class "Default")
      (node (ref "J41") (pin "GND1") (pinfunction "GND_GND1") (pintype "passive"))
      (node (ref "J41") (pin "GND2") (pinfunction "GND_GND2") (pintype "passive"))
      (node (ref "J41") (pin "GND3") (pinfunction "GND_GND3") (pintype "passive"))
      (node (ref "J41") (pin "GND4") (pinfunction "GND_GND4") (pintype "passive"))
      (node (ref "J41") (pin "GND5") (pinfunction "GND_GND5") (pintype "passive"))
      (node (ref "U41A") (pin "1") (pinfunction "1.OUT_1") (pintype "passive"))
      (node (ref "U41A") (pin "2") (pinfunction "2.IN-_2") (pintype "passive"))
    )
    (net (code "95") (name "VBIAS2") (class "Default")
      (node (ref "J42") (pin "GND1") (pinfunction "GND_GND1") (pintype "passive"))
      (node (ref "J42") (pin "GND2") (pinfunction "GND_GND2") (pintype "passive"))
      (node (ref "J42") (pin "GND3") (pinfunction "GND_GND3") (pintype "passive"))
      (node (ref "J42") (pin "GND4") (pinfunction "GND_GND4") (pintype "passive"))
      (node (ref "J42") (pin "GND5") (pinfunction "GND_GND5") (pintype "passive"))
      (node (ref "U42A") (pin "1") (pinfunction "1.OUT_1") (pintype "passive"))
      (node (ref "U42A") (pin "2") (pinfunction "2.IN-_2") (pintype "passive"))
    )
    (net (code "96") (name "VCC") (class "Default")
      (node (ref "C41R") (pin "1") (pinfunction "1_1") (pintype "passive"))
      (node (ref "L40A") (pin "1") (pinfunction "1_1") (pintype "passive"))
      (node (ref "L41A") (pin "1") (pinfunction "1_1") (pintype "passive"))
      (node (ref "L42A") (pin "1") (pinfunction "1_1") (pintype "passive"))
      (node (ref "U40R") (pin "5") (pinfunction "5.VOUT_5") (pintype "passive"))
    )
    (net (code "97") (name "VCCA") (class "Default")
      (node (ref "C31R") (pin "1") (pinfunction "1_1") (pintype "passive"))
      (node (ref "L30A") (pin "1") (pinfunction "1_1") (pintype "passive"))
      (node (ref "L31A") (pin "1") (pinfunction "1_1") (pintype "passive"))
      (node (ref "L32A") (pin "1") (pinfunction "1_1") (pintype "passive"))
      (node (ref "U30R") (pin "5") (pinfunction "5.VOUT_5") (pintype "passive"))
    )
    (net (code "98") (name "VCC_VREF") (class "Default")
      (node (ref "C11R") (pin "1") (pinfunction "1_1") (pintype "passive"))
      (node (ref "L10R") (pin "1") (pinfunction "1_1") (pintype "passive"))
      (node (ref "L30M") (pin "1") (pinfunction "1_1") (pintype "passive"))
      (node (ref "U10R") (pin "5") (pinfunction "5.VOUT_5") (pintype "passive"))
    )
    (net (code "99") (name "VDD_3V3") (class "Default")
      (node (ref "C01O") (pin "1") (pinfunction "1_1") (pintype "passive"))
      (node (ref "C02O") (pin "1") (pinfunction "1_1") (pintype "passive"))
      (node (ref "C10A") (pin "1") (pinfunction "1_1") (pintype "passive"))
      (node (ref "C10B") (pin "1") (pinfunction "1_1") (pintype "passive"))
      (node (ref "C10C") (pin "1") (pinfunction "1_1") (pintype "passive"))
      (node (ref "C10D") (pin "1") (pinfunction "1_1") (pintype "passive"))
      (node (ref "C10R") (pin "1") (pinfunction "1_1") (pintype "passive"))
      (node (ref "C11D") (pin "1") (pinfunction "1_1") (pintype "passive"))
      (node (ref "C12D") (pin "1") (pinfunction "1_1") (pintype "passive"))
      (node (ref "C13D") (pin "1") (pinfunction "1_1") (pintype "passive"))
      (node (ref "C14D") (pin "1") (pinfunction "1_1") (pintype "passive"))
      (node (ref "C15D") (pin "1") (pinfunction "1_1") (pintype "passive"))
      (node (ref "C20D") (pin "1") (pinfunction "1_1") (pintype "passive"))
      (node (ref "C21D") (pin "1") (pinfunction "1_1") (pintype "passive"))
      (node (ref "C30R") (pin "1") (pinfunction "1_1") (pintype "passive"))
      (node (ref "C40R") (pin "1") (pinfunction "1_1") (pintype "passive"))
      (node (ref "C60D") (pin "1") (pinfunction "1_1") (pintype "passive"))
      (node (ref "C61D") (pin "1") (pinfunction "1_1") (pintype "passive"))
      (node (ref "J20D") (pin "9") (pinfunction "9.3V3_IN_9") (pintype "passive"))
      (node (ref "R01F") (pin "2") (pinfunction "2_2") (pintype "passive"))
      (node (ref "R02L") (pin "1") (pinfunction "1_1") (pintype "passive"))
      (node (ref "R10I") (pin "1") (pinfunction "1_1") (pintype "passive"))
      (node (ref "R11I") (pin "1") (pinfunction "1_1") (pintype "passive"))
      (node (ref "R12L") (pin "1") (pinfunction "1_1") (pintype "passive"))
      (node (ref "R13L") (pin "1") (pinfunction "1_1") (pintype "passive"))
      (node (ref "U01") (pin "7") (pinfunction "7.VOUT_7") (pintype "passive"))
      (node (ref "U10") (pin "100") (pinfunction "100.VDD_100") (pintype "passive"))
      (node (ref "U10") (pin "11") (pinfunction "11.VDD_11") (pintype "passive"))
      (node (ref "U10") (pin "19") (pinfunction "19.VDD_19") (pintype "passive"))
      (node (ref "U10") (pin "22") (pinfunction "22.VDDA_22") (pintype "passive"))
      (node (ref "U10") (pin "28") (pinfunction "28.VDD_28") (pintype "passive"))
      (node (ref "U10") (pin "50") (pinfunction "50.VDD_50") (pintype "passive"))
      (node (ref "U10") (pin "6") (pinfunction "6.VBAT_6") (pintype "passive"))
      (node (ref "U10") (pin "75") (pinfunction "75.VDD_75") (pintype "passive"))
      (node (ref "U10R") (pin "3") (pinfunction "3.ENA_3") (pintype "passive"))
      (node (ref "U10R") (pin "4") (pinfunction "4.VIN_4") (pintype "passive"))
      (node (ref "U11") (pin "4") (pinfunction "4.VCC_4") (pintype "passive"))
      (node (ref "U20") (pin "8") (pinfunction "8.VDD_8") (pintype "passive"))
      (node (ref "U30R") (pin "4") (pinfunction "4.VIN_4") (pintype "passive"))
      (node (ref "U40R") (pin "4") (pinfunction "4.VIN_4") (pintype "passive"))
      (node (ref "U60") (pin "1") (pinfunction "1.VDD_1") (pintype "passive"))
      (node (ref "U61") (pin "4") (pinfunction "4.VDD_4") (pintype "passive"))
    )
    (net (code "100") (name "VDD_24V") (class "Default")
      (node (ref "C01I") (pin "1") (pinfunction "1_1") (pintype "passive"))
      (node (ref "C02I") (pin "1") (pinfunction "1_1") (pintype "passive"))
      (node (ref "J20B") (pin "A4") (pinfunction "A4.VBUS_A4") (pintype "passive"))
      (node (ref "J20B") (pin "A5") (pinfunction "A5.NU_A5") (pintype "passive"))
      (node (ref "J20B") (pin "A8") (pinfunction "A8.NU_A8") (pintype "passive"))
      (node (ref "J20B") (pin "A9") (pinfunction "A9.VBUS_A9") (pintype "passive"))
      (node (ref "J20B") (pin "B4") (pinfunction "B4.VBUS_B4") (pintype "passive"))
      (node (ref "J20B") (pin "B5") (pinfunction "B5.NU_B5") (pintype "passive"))
      (node (ref "J20B") (pin "B8") (pinfunction "B8.NU_B8") (pintype "passive"))
      (node (ref "J20B") (pin "B9") (pinfunction "B9.VBUS_B9") (pintype "passive"))
      (node (ref "J21B") (pin "A4") (pinfunction "A4.VBUS_A4") (pintype "passive"))
      (node (ref "J21B") (pin "A5") (pinfunction "A5.NU_A5") (pintype "passive"))
      (node (ref "J21B") (pin "A8") (pinfunction "A8.NU_A8") (pintype "passive"))
      (node (ref "J21B") (pin "A9") (pinfunction "A9.VBUS_A9") (pintype "passive"))
      (node (ref "J21B") (pin "B4") (pinfunction "B4.VBUS_B4") (pintype "passive"))
      (node (ref "J21B") (pin "B5") (pinfunction "B5.NU_B5") (pintype "passive"))
      (node (ref "J21B") (pin "B8") (pinfunction "B8.NU_B8") (pintype "passive"))
      (node (ref "J21B") (pin "B9") (pinfunction "B9.VBUS_B9") (pintype "passive"))
      (node (ref "R01L") (pin "1") (pinfunction "1_1") (pintype "passive"))
      (node (ref "R50P") (pin "1") (pinfunction "1_1") (pintype "passive"))
      (node (ref "R50S") (pin "1") (pinfunction "1_1") (pintype "passive"))
      (node (ref "R51P") (pin "1") (pinfunction "1_1") (pintype "passive"))
      (node (ref "R52P") (pin "1") (pinfunction "1_1") (pintype "passive"))
      (node (ref "R52S") (pin "1") (pinfunction "1_1") (pintype "passive"))
      (node (ref "R54S") (pin "1") (pinfunction "1_1") (pintype "passive"))
      (node (ref "U01") (pin "1") (pinfunction "1.VIN_1") (pintype "passive"))
    )
    (net (code "101") (name "VX") (class "Default")
      (node (ref "C30M") (pin "1") (pinfunction "1_1") (pintype "passive"))
      (node (ref "L30M") (pin "2") (pinfunction "2_2") (pintype "passive"))
      (node (ref "U30M") (pin "5") (pinfunction "5.EN_5") (pintype "passive"))
      (node (ref "U30M") (pin "6") (pinfunction "6.VDD_6") (pintype "passive"))
    )
    (net (code "102") (name "unconnected-(J20B-A3.NU-PadA3)") (class "Default")
      (node (ref "J20B") (pin "A3") (pinfunction "A3.NU_A3") (pintype "passive"))
    )
    (net (code "103") (name "unconnected-(J20B-A10.NU-PadA10)") (class "Default")
      (node (ref "J20B") (pin "A10") (pinfunction "A10.NU_A10") (pintype "passive"))
    )
    (net (code "104") (name "unconnected-(J20B-B3.NU-PadB3)") (class "Default")
      (node (ref "J20B") (pin "B3") (pinfunction "B3.NU_B3") (pintype "passive"))
    )
    (net (code "105") (name "unconnected-(J20B-B6.DP2-PadB6)") (class "Default")
      (node (ref "J20B") (pin "B6") (pinfunction "B6.DP2_B6") (pintype "passive"))
    )
    (net (code "106") (name "unconnected-(J20B-B7.DN2-PadB7)") (class "Default")
      (node (ref "J20B") (pin "B7") (pinfunction "B7.DN2_B7") (pintype "passive"))
    )
    (net (code "107") (name "unconnected-(J20B-B10.NU-PadB10)") (class "Default")
      (node (ref "J20B") (pin "B10") (pinfunction "B10.NU_B10") (pintype "passive"))
    )
    (net (code "108") (name "unconnected-(J20D-5.IO3-Pad5)") (class "Default")
      (node (ref "J20D") (pin "5") (pinfunction "5.IO3_5") (pintype "passive"))
    )
    (net (code "109") (name "unconnected-(J20D-6.IO2-Pad6)") (class "Default")
      (node (ref "J20D") (pin "6") (pinfunction "6.IO2_6") (pintype "passive"))
    )
    (net (code "110") (name "unconnected-(J20D-7.NC-Pad7)") (class "Default")
      (node (ref "J20D") (pin "7") (pinfunction "7.NC_7") (pintype "passive"))
    )
    (net (code "111") (name "unconnected-(J20D-8.NC-Pad8)") (class "Default")
      (node (ref "J20D") (pin "8") (pinfunction "8.NC_8") (pintype "passive"))
    )
    (net (code "112") (name "unconnected-(J20D-10.VBUS-Pad10)") (class "Default")
      (node (ref "J20D") (pin "10") (pinfunction "10.VBUS_10") (pintype "passive"))
    )
    (net (code "113") (name "unconnected-(J20D-15.PWM-Pad15)") (class "Default")
      (node (ref "J20D") (pin "15") (pinfunction "15.PWM_15") (pintype "passive"))
    )
    (net (code "114") (name "unconnected-(J20D-16.NC-Pad16)") (class "Default")
      (node (ref "J20D") (pin "16") (pinfunction "16.NC_16") (pintype "passive"))
    )
    (net (code "115") (name "unconnected-(J21B-A3.NU-PadA3)") (class "Default")
      (node (ref "J21B") (pin "A3") (pinfunction "A3.NU_A3") (pintype "passive"))
    )
    (net (code "116") (name "unconnected-(J21B-A10.NU-PadA10)") (class "Default")
      (node (ref "J21B") (pin "A10") (pinfunction "A10.NU_A10") (pintype "passive"))
    )
    (net (code "117") (name "unconnected-(J21B-B3.NU-PadB3)") (class "Default")
      (node (ref "J21B") (pin "B3") (pinfunction "B3.NU_B3") (pintype "passive"))
    )
    (net (code "118") (name "unconnected-(J21B-B6.DP2-PadB6)") (class "Default")
      (node (ref "J21B") (pin "B6") (pinfunction "B6.DP2_B6") (pintype "passive"))
    )
    (net (code "119") (name "unconnected-(J21B-B7.DN2-PadB7)") (class "Default")
      (node (ref "J21B") (pin "B7") (pinfunction "B7.DN2_B7") (pintype "passive"))
    )
    (net (code "120") (name "unconnected-(J21B-B10.NU-PadB10)") (class "Default")
      (node (ref "J21B") (pin "B10") (pinfunction "B10.NU_B10") (pintype "passive"))
    )
    (net (code "121") (name "unconnected-(U01-3.ENA-Pad3)") (class "Default")
      (node (ref "U01") (pin "3") (pinfunction "3.ENA_3") (pintype "passive"))
    )
    (net (code "122") (name "unconnected-(U10-7.PC13-Pad7)") (class "Default")
      (node (ref "U10") (pin "7") (pinfunction "7.PC13_7") (pintype "passive"))
    )
    (net (code "123") (name "unconnected-(U10-8.PC14-Pad8)") (class "Default")
      (node (ref "U10") (pin "8") (pinfunction "8.PC14_8") (pintype "passive"))
    )
    (net (code "124") (name "unconnected-(U10-9.PC15-Pad9)") (class "Default")
      (node (ref "U10") (pin "9") (pinfunction "9.PC15_9") (pintype "passive"))
    )
    (net (code "125") (name "unconnected-(U10-12.OSC_IN-Pad12)") (class "Default")
      (node (ref "U10") (pin "12") (pinfunction "12.OSC_IN_12") (pintype "passive"))
    )
    (net (code "126") (name "unconnected-(U10-13.OSC_OUT-Pad13)") (class "Default")
      (node (ref "U10") (pin "13") (pinfunction "13.OSC_OUT_13") (pintype "passive"))
    )
    (net (code "127") (name "unconnected-(U10-37.PB2-Pad37)") (class "Default")
      (node (ref "U10") (pin "37") (pinfunction "37.PB2_37") (pintype "passive"))
    )
    (net (code "128") (name "unconnected-(U10-41.PE10-Pad41)") (class "Default")
      (node (ref "U10") (pin "41") (pinfunction "41.PE10_41") (pintype "passive"))
    )
    (net (code "129") (name "unconnected-(U10-42.PE11-Pad42)") (class "Default")
      (node (ref "U10") (pin "42") (pinfunction "42.PE11_42") (pintype "passive"))
    )
    (net (code "130") (name "unconnected-(U10-43.PE12-Pad43)") (class "Default")
      (node (ref "U10") (pin "43") (pinfunction "43.PE12_43") (pintype "passive"))
    )
    (net (code "131") (name "unconnected-(U10-44.PE13-Pad44)") (class "Default")
      (node (ref "U10") (pin "44") (pinfunction "44.PE13_44") (pintype "passive"))
    )
    (net (code "132") (name "unconnected-(U10-45.PE14-Pad45)") (class "Default")
      (node (ref "U10") (pin "45") (pinfunction "45.PE14_45") (pintype "passive"))
    )
    (net (code "133") (name "unconnected-(U10-46.PE15-Pad46)") (class "Default")
      (node (ref "U10") (pin "46") (pinfunction "46.PE15_46") (pintype "passive"))
    )
    (net (code "134") (name "unconnected-(U10-52.PB13-Pad52)") (class "Default")
      (node (ref "U10") (pin "52") (pinfunction "52.PB13_52") (pintype "passive"))
    )
    (net (code "135") (name "unconnected-(U10-53.PB14-Pad53)") (class "Default")
      (node (ref "U10") (pin "53") (pinfunction "53.PB14_53") (pintype "passive"))
    )
    (net (code "136") (name "unconnected-(U10-54.PB15-Pad54)") (class "Default")
      (node (ref "U10") (pin "54") (pinfunction "54.PB15_54") (pintype "passive"))
    )
    (net (code "137") (name "unconnected-(U10-55.PD8-Pad55)") (class "Default")
      (node (ref "U10") (pin "55") (pinfunction "55.PD8_55") (pintype "passive"))
    )
    (net (code "138") (name "unconnected-(U10-56.PD9-Pad56)") (class "Default")
      (node (ref "U10") (pin "56") (pinfunction "56.PD9_56") (pintype "passive"))
    )
    (net (code "139") (name "unconnected-(U10-57.PD10-Pad57)") (class "Default")
      (node (ref "U10") (pin "57") (pinfunction "57.PD10_57") (pintype "passive"))
    )
    (net (code "140") (name "unconnected-(U10-58.PD11-Pad58)") (class "Default")
      (node (ref "U10") (pin "58") (pinfunction "58.PD11_58") (pintype "passive"))
    )
    (net (code "141") (name "unconnected-(U10-59.PD12-Pad59)") (class "Default")
      (node (ref "U10") (pin "59") (pinfunction "59.PD12_59") (pintype "passive"))
    )
    (net (code "142") (name "unconnected-(U10-60.PD13-Pad60)") (class "Default")
      (node (ref "U10") (pin "60") (pinfunction "60.PD13_60") (pintype "passive"))
    )
    (net (code "143") (name "unconnected-(U10-61.PD14-Pad61)") (class "Default")
      (node (ref "U10") (pin "61") (pinfunction "61.PD14_61") (pintype "passive"))
    )
    (net (code "144") (name "unconnected-(U10-62.PD15-Pad62)") (class "Default")
      (node (ref "U10") (pin "62") (pinfunction "62.PD15_62") (pintype "passive"))
    )
    (net (code "145") (name "unconnected-(U10-63.PC6-Pad63)") (class "Default")
      (node (ref "U10") (pin "63") (pinfunction "63.PC6_63") (pintype "passive"))
    )
    (net (code "146") (name "unconnected-(U10-64.PC7-Pad64)") (class "Default")
      (node (ref "U10") (pin "64") (pinfunction "64.PC7_64") (pintype "passive"))
    )
    (net (code "147") (name "unconnected-(U10-65.PC8-Pad65)") (class "Default")
      (node (ref "U10") (pin "65") (pinfunction "65.PC8_65") (pintype "passive"))
    )
    (net (code "148") (name "unconnected-(U10-66.PC9-Pad66)") (class "Default")
      (node (ref "U10") (pin "66") (pinfunction "66.PC9_66") (pintype "passive"))
    )
    (net (code "149") (name "unconnected-(U10-67.PA8-Pad67)") (class "Default")
      (node (ref "U10") (pin "67") (pinfunction "67.PA8_67") (pintype "passive"))
    )
    (net (code "150") (name "unconnected-(U10-70.PA11-Pad70)") (class "Default")
      (node (ref "U10") (pin "70") (pinfunction "70.PA11_70") (pintype "passive"))
    )
    (net (code "151") (name "unconnected-(U10-71.PA12-Pad71)") (class "Default")
      (node (ref "U10") (pin "71") (pinfunction "71.PA12_71") (pintype "passive"))
    )
    (net (code "152") (name "unconnected-(U10-77.PA15-Pad77)") (class "Default")
      (node (ref "U10") (pin "77") (pinfunction "77.PA15_77") (pintype "passive"))
    )
    (net (code "153") (name "unconnected-(U10-84.PD3-Pad84)") (class "Default")
      (node (ref "U10") (pin "84") (pinfunction "84.PD3_84") (pintype "passive"))
    )
    (net (code "154") (name "unconnected-(U10-85.PD4-Pad85)") (class "Default")
      (node (ref "U10") (pin "85") (pinfunction "85.PD4_85") (pintype "passive"))
    )
    (net (code "155") (name "unconnected-(U10-86.PD5-Pad86)") (class "Default")
      (node (ref "U10") (pin "86") (pinfunction "86.PD5_86") (pintype "passive"))
    )
    (net (code "156") (name "unconnected-(U10-87.PD6-Pad87)") (class "Default")
      (node (ref "U10") (pin "87") (pinfunction "87.PD6_87") (pintype "passive"))
    )
    (net (code "157") (name "unconnected-(U10-88.PD7-Pad88)") (class "Default")
      (node (ref "U10") (pin "88") (pinfunction "88.PD7_88") (pintype "passive"))
    )
    (net (code "158") (name "unconnected-(U10-89.PB3-Pad89)") (class "Default")
      (node (ref "U10") (pin "89") (pinfunction "89.PB3_89") (pintype "passive"))
    )
    (net (code "159") (name "unconnected-(U10-90.PB4-Pad90)") (class "Default")
      (node (ref "U10") (pin "90") (pinfunction "90.PB4_90") (pintype "passive"))
    )
    (net (code "160") (name "unconnected-(U10-91.PB5-Pad91)") (class "Default")
      (node (ref "U10") (pin "91") (pinfunction "91.PB5_91") (pintype "passive"))
    )
    (net (code "161") (name "unconnected-(U10R-1.REF-Pad1)") (class "Default")
      (node (ref "U10R") (pin "1") (pinfunction "1.REF_1") (pintype "passive"))
    )
    (net (code "162") (name "unconnected-(U11-3.32KHZ-Pad3)") (class "Default")
      (node (ref "U11") (pin "3") (pinfunction "3.32KHZ_3") (pintype "passive"))
    )
    (net (code "163") (name "unconnected-(U11-5.INT{slash}SQW-Pad5)") (class "Default")
      (node (ref "U11") (pin "5") (pinfunction "5.INT/SQW_5") (pintype "passive"))
    )
    (net (code "164") (name "unconnected-(U11-6.RST-Pad6)") (class "Default")
      (node (ref "U11") (pin "6") (pinfunction "6.RST_6") (pintype "passive"))
    )
    (net (code "165") (name "unconnected-(U30M-9.S2-Pad9)") (class "Default")
      (node (ref "U30M") (pin "9") (pinfunction "9.S2_9") (pintype "passive"))
    )
    (net (code "166") (name "unconnected-(U30R-1.REF-Pad1)") (class "Default")
      (node (ref "U30R") (pin "1") (pinfunction "1.REF_1") (pintype "passive"))
    )
    (net (code "167") (name "unconnected-(U40R-1.REF-Pad1)") (class "Default")
      (node (ref "U40R") (pin "1") (pinfunction "1.REF_1") (pintype "passive"))
    )
    (net (code "168") (name "unconnected-(U60-6.NU-Pad6)") (class "Default")
      (node (ref "U60") (pin "6") (pinfunction "6.NU_6") (pintype "passive"))
    )
    (net (code "169") (name "unconnected-(U60-7.SEL-Pad7)") (class "Default")
      (node (ref "U60") (pin "7") (pinfunction "7.SEL_7") (pintype "passive"))
    )
    (net (code "170") (name "~{PH0_OFF}") (class "Default")
      (node (ref "C40B") (pin "2") (pinfunction "2_2") (pintype "passive"))
      (node (ref "R40B") (pin "2") (pinfunction "2_2") (pintype "passive"))
      (node (ref "R41B") (pin "1") (pinfunction "1_1") (pintype "passive"))
      (node (ref "U10") (pin "5") (pinfunction "5.PE6_5") (pintype "passive"))
      (node (ref "U40A") (pin "3") (pinfunction "3.IN+_3") (pintype "passive"))
    )
    (net (code "171") (name "~{PH1_OFF}") (class "Default")
      (node (ref "C41B") (pin "2") (pinfunction "2_2") (pintype "passive"))
      (node (ref "R42B") (pin "2") (pinfunction "2_2") (pintype "passive"))
      (node (ref "R43B") (pin "1") (pinfunction "1_1") (pintype "passive"))
      (node (ref "U10") (pin "2") (pinfunction "2.PE3_2") (pintype "passive"))
      (node (ref "U41A") (pin "3") (pinfunction "3.IN+_3") (pintype "passive"))
    )
    (net (code "172") (name "~{PH2_OFF}") (class "Default")
      (node (ref "C42B") (pin "2") (pinfunction "2_2") (pintype "passive"))
      (node (ref "R44B") (pin "2") (pinfunction "2_2") (pintype "passive"))
      (node (ref "R45B") (pin "1") (pinfunction "1_1") (pintype "passive"))
      (node (ref "U10") (pin "97") (pinfunction "97.PE0_97") (pintype "passive"))
      (node (ref "U42A") (pin "3") (pinfunction "3.IN+_3") (pintype "passive"))
    )
    (net (code "173") (name "~{RST}") (class "Default")
      (node (ref "C10") (pin "1") (pinfunction "1_1") (pintype "passive"))
      (node (ref "RESET") (pin "2") (pinfunction "3-4_2") (pintype "passive"))
      (node (ref "U10") (pin "14") (pinfunction "14.~{RST}_14") (pintype "passive"))
    )
    (net (code "174") (name "~{RTC_SEL}") (class "Default")
      (node (ref "U10") (pin "40") (pinfunction "40.PE9_40") (pintype "passive"))
      (node (ref "U11") (pin "1") (pinfunction "1.CS_1") (pintype "passive"))
    )
    (net (code "175") (name "~{TFT_INT}") (class "Default")
      (node (ref "J20D") (pin "14") (pinfunction "14.~{INT}_14") (pintype "passive"))
      (node (ref "U10") (pin "83") (pinfunction "83.PD2_83") (pintype "passive"))
    )
    (net (code "176") (name "~{TFT_PD}") (class "Default")
      (node (ref "J20D") (pin "13") (pinfunction "13.~{PD}_13") (pintype "passive"))
      (node (ref "U10") (pin "82") (pinfunction "82.PD1_82") (pintype "passive"))
    )
    (net (code "177") (name "~{TFT_SEL}") (class "Default")
      (node (ref "J20D") (pin "2") (pinfunction "2.~{CS}_2") (pintype "passive"))
      (node (ref "U10") (pin "81") (pinfunction "81.PD0_81") (pintype "passive"))
    )
  )
)
